# Flatsat_v1.net
KiCad netlist of a schematic drawn in EAGLE
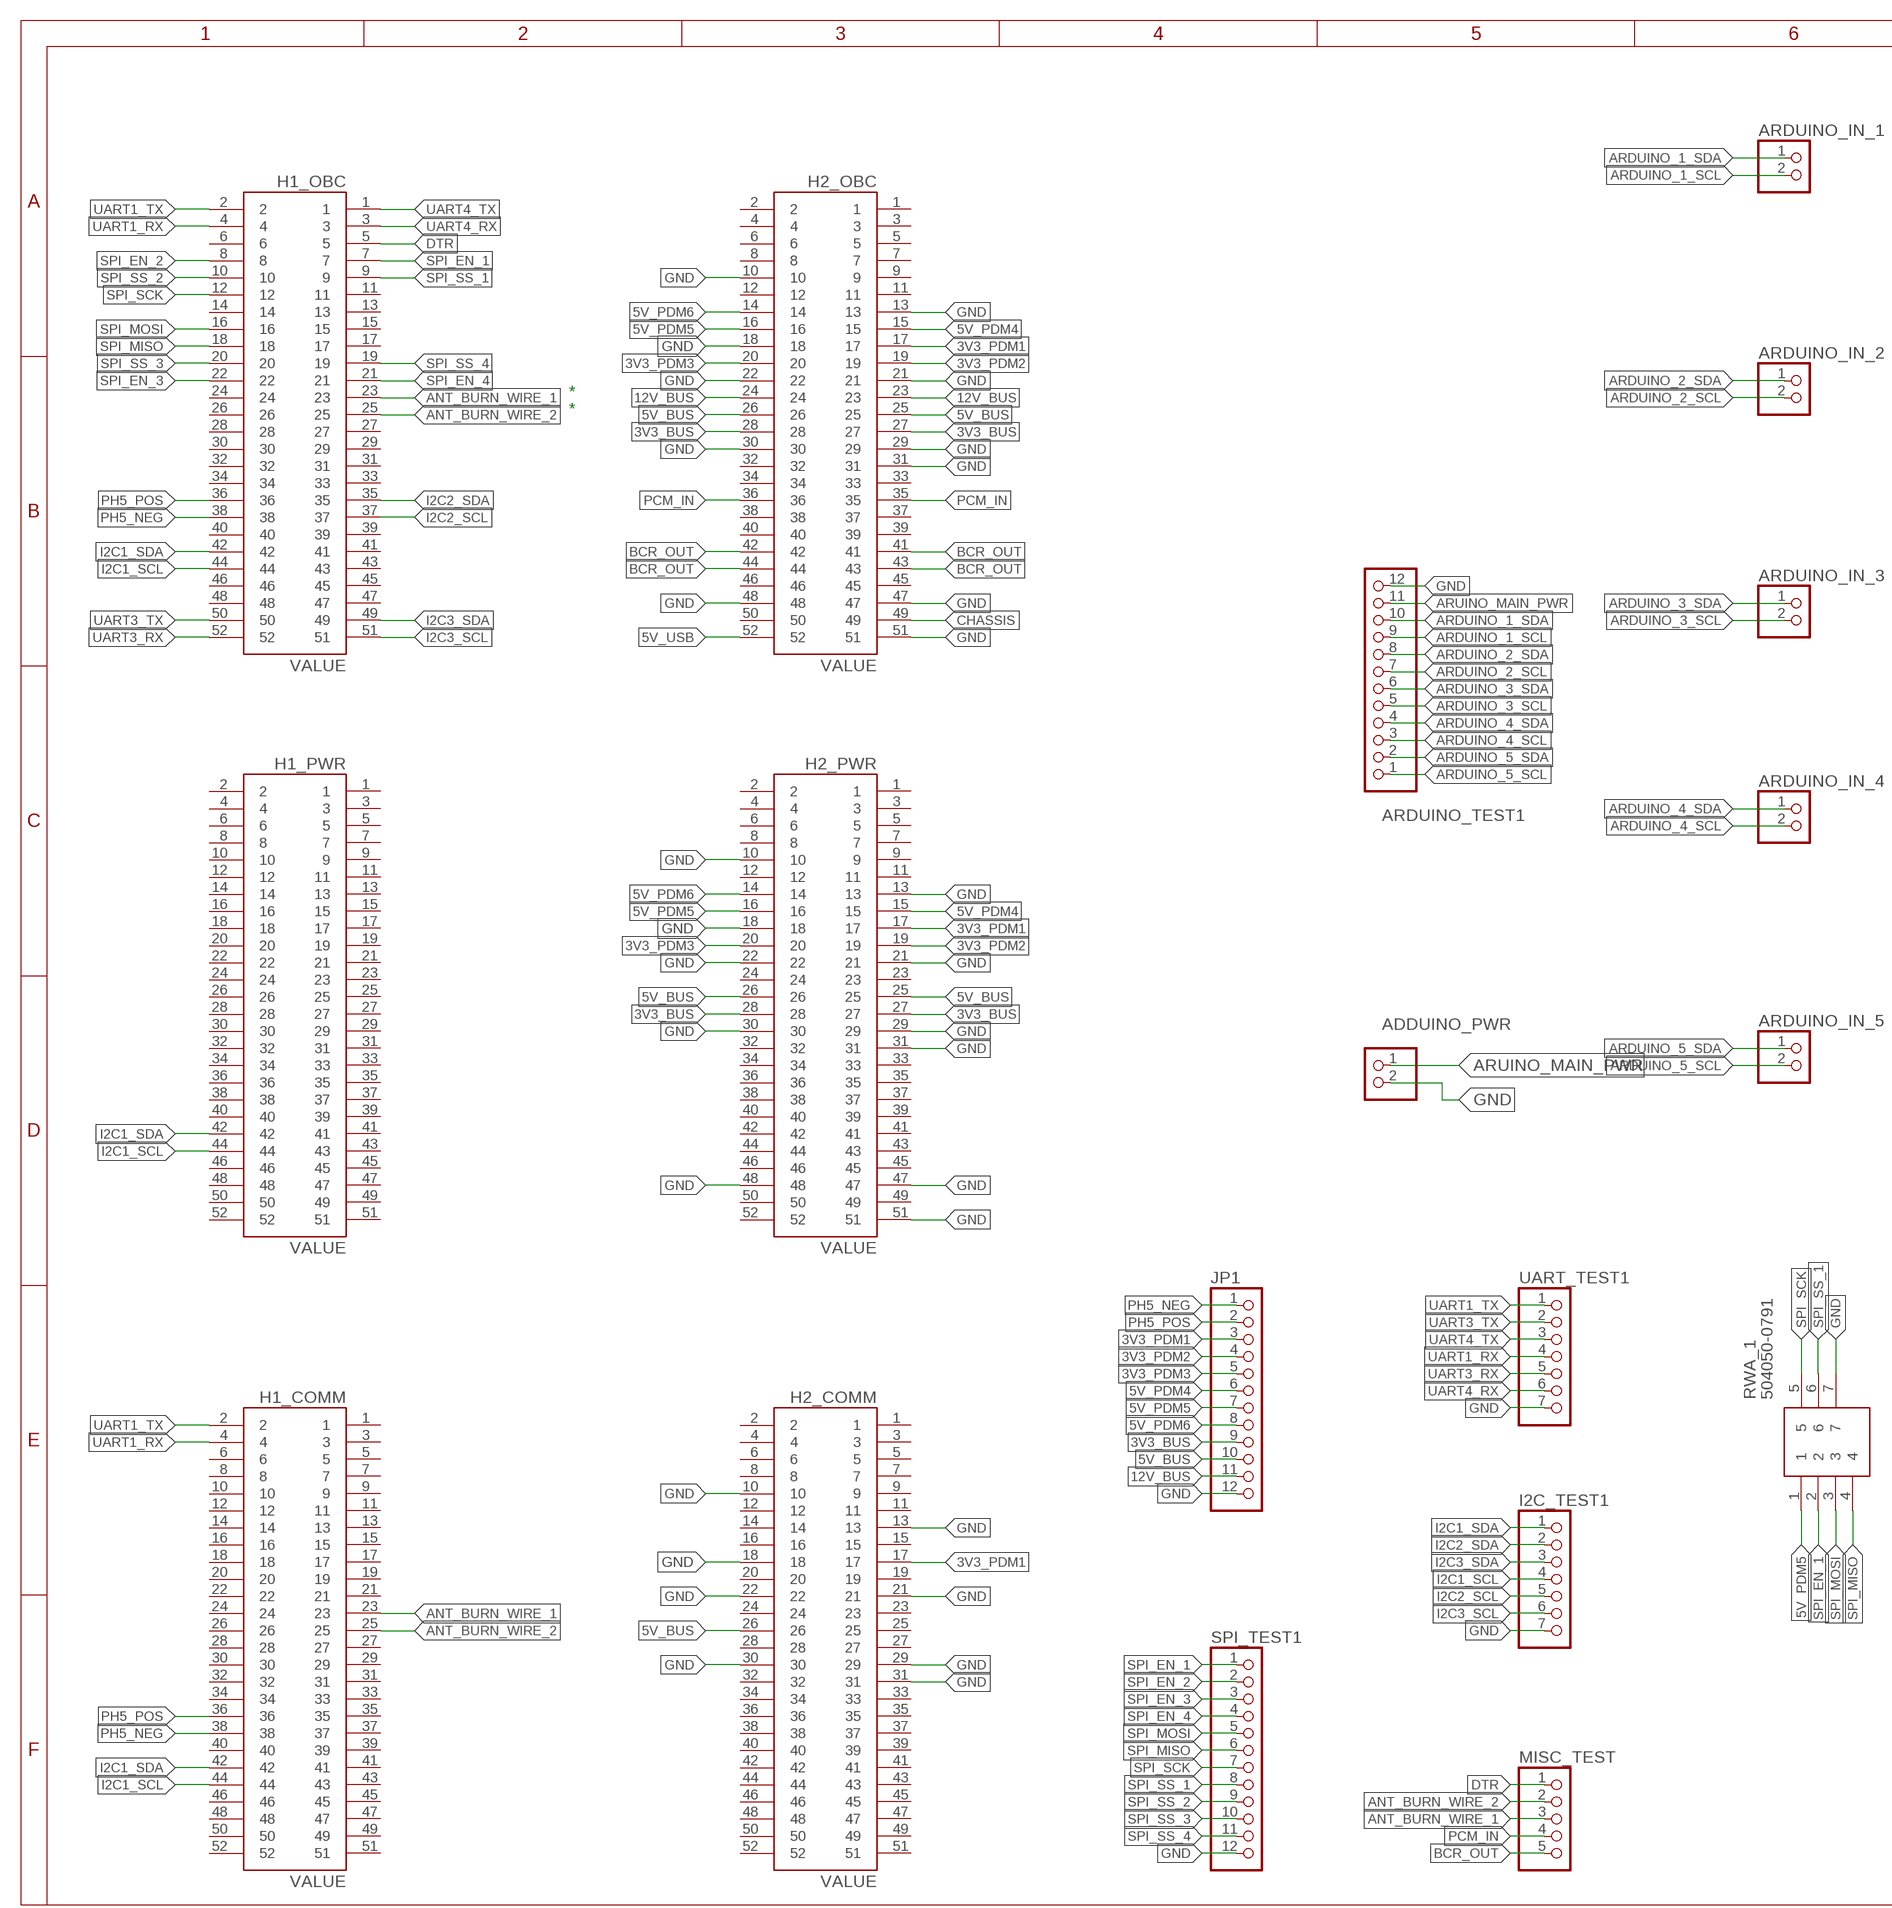
[diagram p0: schematic, sheet 1, part 1 of 2]
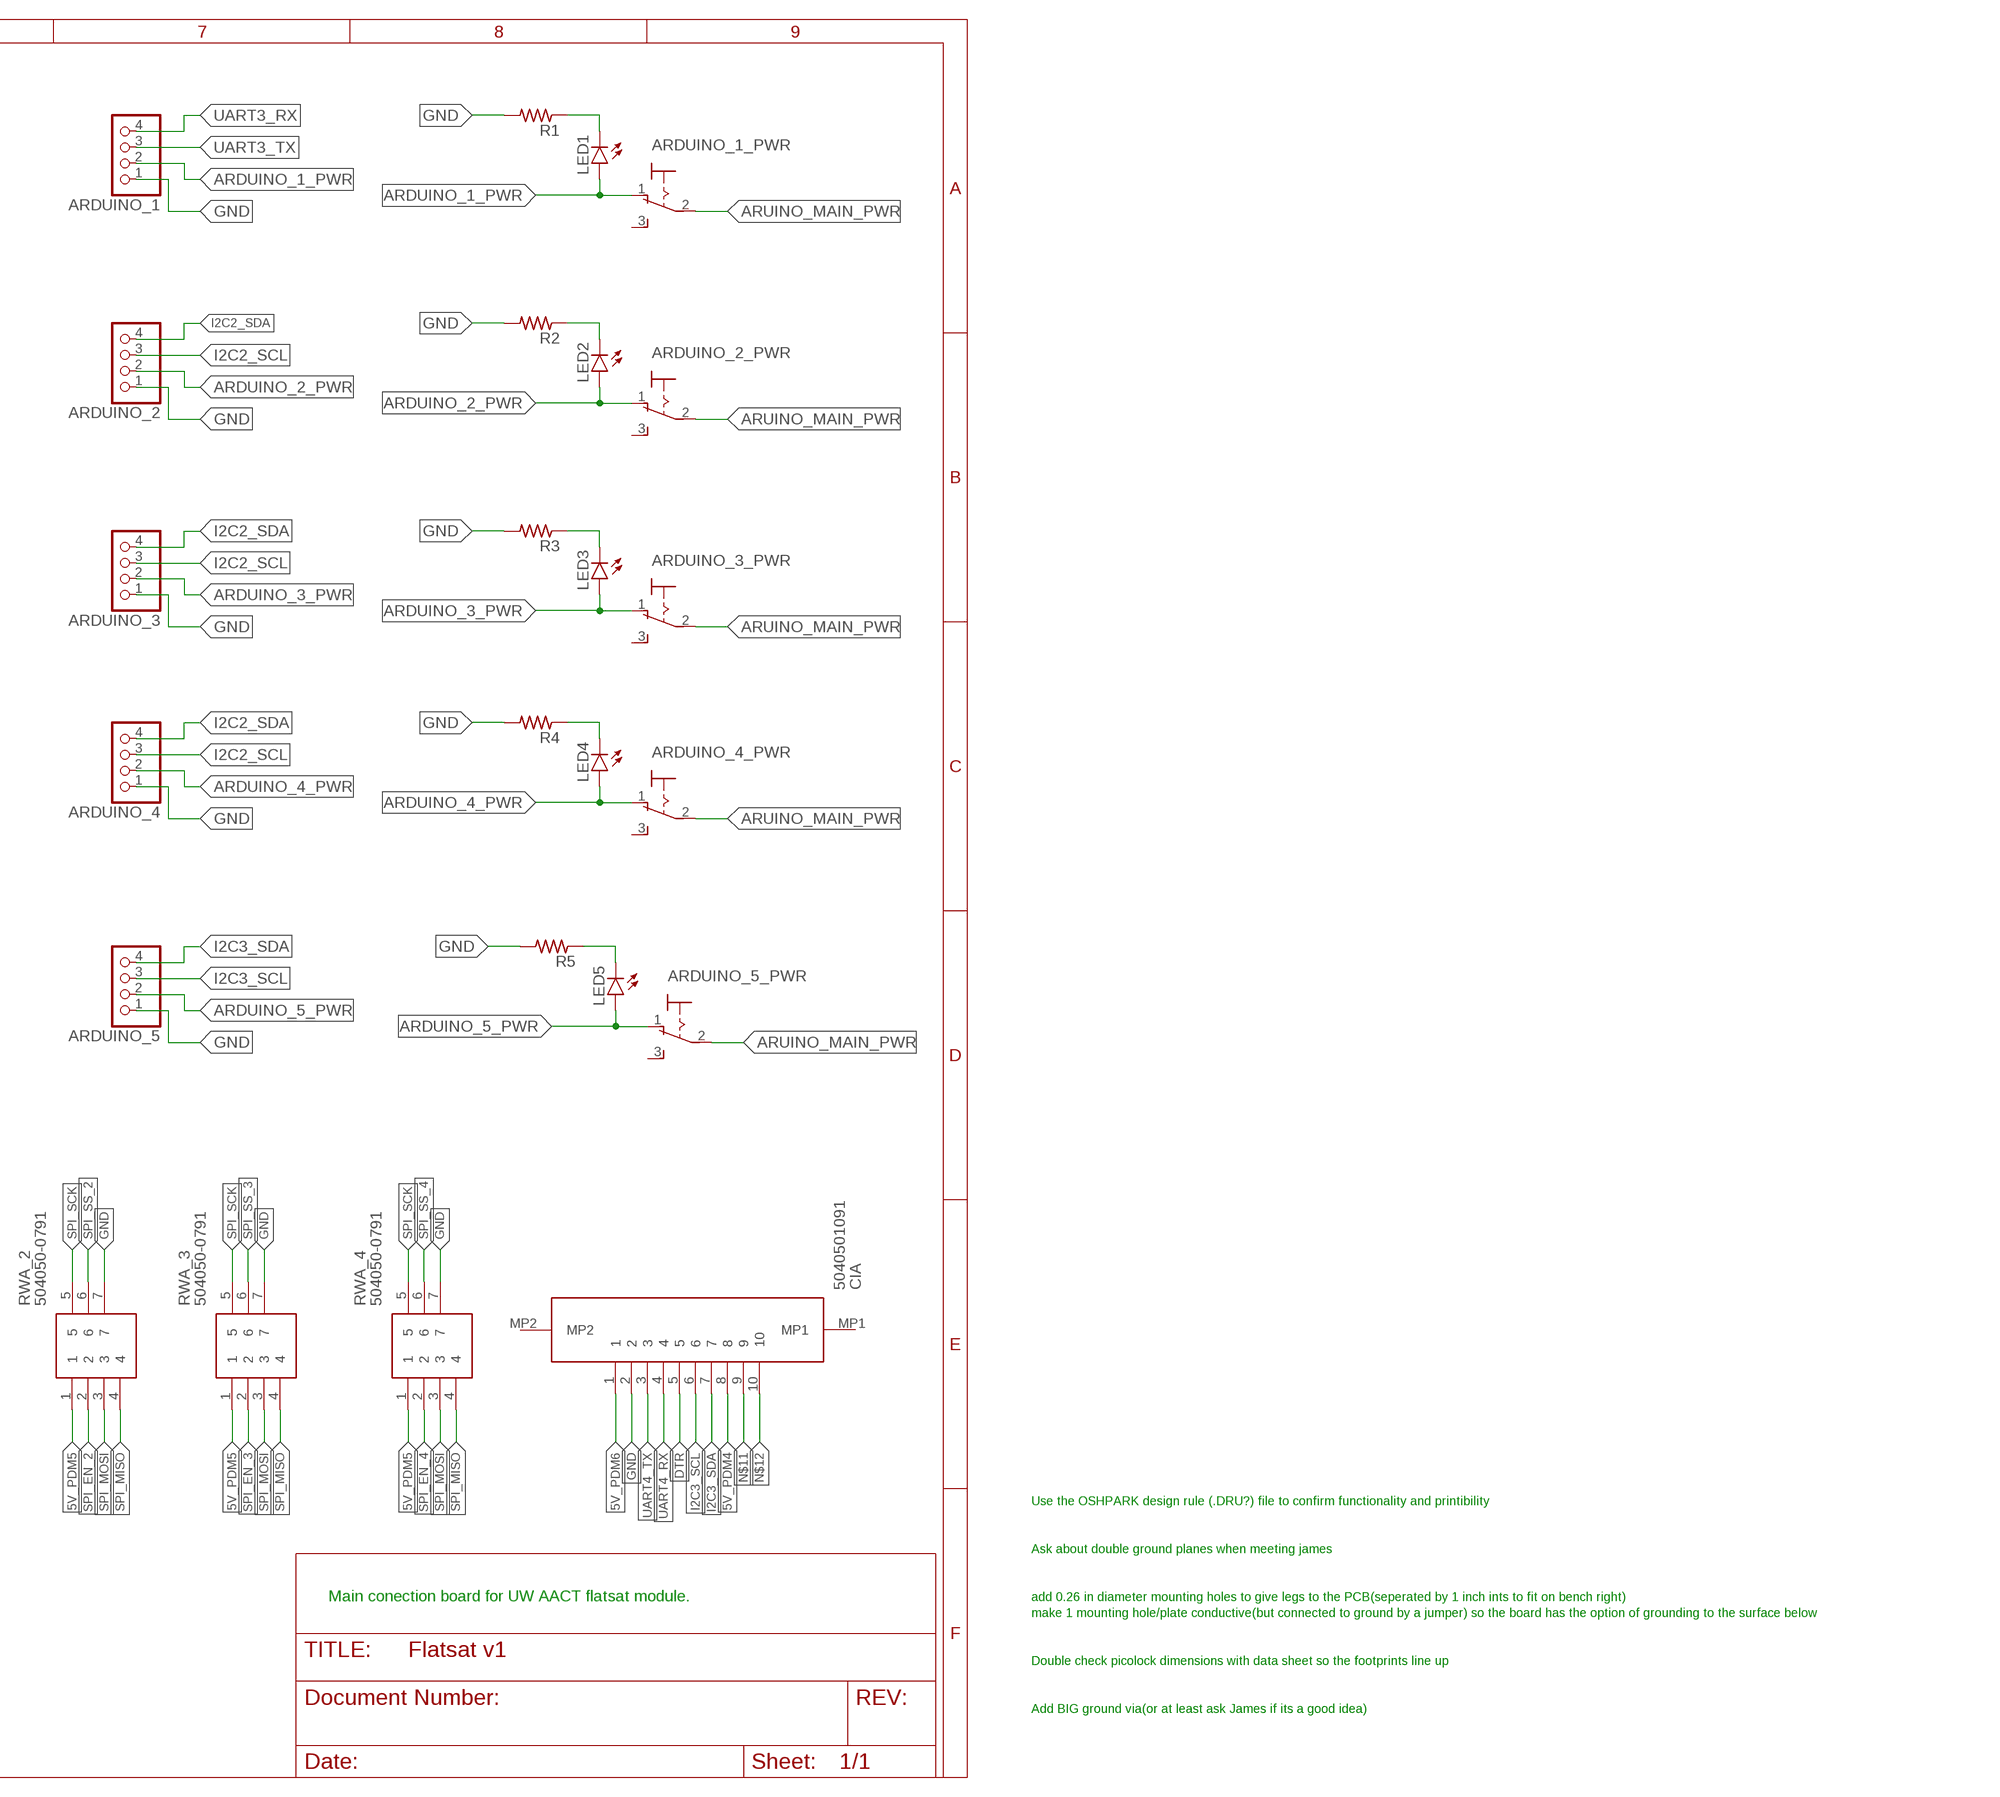
[diagram p1: schematic, sheet 1, part 2 of 2]

(export (version "E")
  (design (tool "Eeschema 10.0.6"))
  (components
    (comp (ref "ADDUINO_PWR")
      (value "PINHD-1X2")
      (footprint "eagle-import:1X02")
      (libsource (lib "eagle-import") (part "PINHD-1X2"))
    )
    (comp (ref "ARDUINO_1")
      (value "PINHD-1X4")
      (footprint "eagle-import:1X04")
      (libsource (lib "eagle-import") (part "PINHD-1X4"))
    )
    (comp (ref "ARDUINO_1_PWR")
      (value "M9040P")
      (footprint "eagle-import:M9040P")
      (libsource (lib "eagle-import") (part "M9040P"))
    )
    (comp (ref "ARDUINO_2")
      (value "PINHD-1X4")
      (footprint "eagle-import:1X04")
      (libsource (lib "eagle-import") (part "PINHD-1X4"))
    )
    (comp (ref "ARDUINO_2_PWR")
      (value "M9040P")
      (footprint "eagle-import:M9040P")
      (libsource (lib "eagle-import") (part "M9040P"))
    )
    (comp (ref "ARDUINO_3")
      (value "PINHD-1X4")
      (footprint "eagle-import:1X04")
      (libsource (lib "eagle-import") (part "PINHD-1X4"))
    )
    (comp (ref "ARDUINO_3_PWR")
      (value "M9040P")
      (footprint "eagle-import:M9040P")
      (libsource (lib "eagle-import") (part "M9040P"))
    )
    (comp (ref "ARDUINO_4")
      (value "PINHD-1X4")
      (footprint "eagle-import:1X04")
      (libsource (lib "eagle-import") (part "PINHD-1X4"))
    )
    (comp (ref "ARDUINO_4_PWR")
      (value "M9040P")
      (footprint "eagle-import:M9040P")
      (libsource (lib "eagle-import") (part "M9040P"))
    )
    (comp (ref "ARDUINO_5")
      (value "PINHD-1X4")
      (footprint "eagle-import:1X04")
      (libsource (lib "eagle-import") (part "PINHD-1X4"))
    )
    (comp (ref "ARDUINO_5_PWR")
      (value "M9040P")
      (footprint "eagle-import:M9040P")
      (libsource (lib "eagle-import") (part "M9040P"))
    )
    (comp (ref "ARDUINO_IN_1")
      (value "PINHD-1X2")
      (footprint "eagle-import:1X02")
      (libsource (lib "eagle-import") (part "PINHD-1X2"))
    )
    (comp (ref "ARDUINO_IN_2")
      (value "PINHD-1X2")
      (footprint "eagle-import:1X02")
      (libsource (lib "eagle-import") (part "PINHD-1X2"))
    )
    (comp (ref "ARDUINO_IN_3")
      (value "PINHD-1X2")
      (footprint "eagle-import:1X02")
      (libsource (lib "eagle-import") (part "PINHD-1X2"))
    )
    (comp (ref "ARDUINO_IN_4")
      (value "PINHD-1X2")
      (footprint "eagle-import:1X02")
      (libsource (lib "eagle-import") (part "PINHD-1X2"))
    )
    (comp (ref "ARDUINO_IN_5")
      (value "PINHD-1X2")
      (footprint "eagle-import:1X02")
      (libsource (lib "eagle-import") (part "PINHD-1X2"))
    )
    (comp (ref "ARDUINO_TEST1")
      (value "PINHD-1X12")
      (footprint "eagle-import:1X12")
      (libsource (lib "eagle-import") (part "PINHD-1X12"))
    )
    (comp (ref "CIA")
      (value "5040501091")
      (footprint "eagle-import:5040501091")
      (libsource (lib "eagle-import") (part "5040501091"))
    )
    (comp (ref "H1_COMM")
      (value "ESQ-126-39-G-D_ESQ-126-39-G-D")
      (footprint "eagle-import:ESQ-126-39-G-D_SAMTEC_ESQ-126-39-G-D")
      (fields
        (field (name "DIGI-KEY_PART_NUMBER") "SAM10462-ND")
        (field (name "MF") "Samtec")
        (field (name "MP") "ESQ-126-39-G-D")
      )
      (libsource (lib "eagle-import") (part "ESQ-126-39-G-D_ESQ-126-39-G-D"))
    )
    (comp (ref "H1_OBC")
      (value "ESQ-126-39-G-D_ESQ-126-39-G-D")
      (footprint "eagle-import:ESQ-126-39-G-D_SAMTEC_ESQ-126-39-G-D")
      (fields
        (field (name "DIGI-KEY_PART_NUMBER") "SAM10462-ND")
        (field (name "MF") "Samtec")
        (field (name "MP") "ESQ-126-39-G-D")
      )
      (libsource (lib "eagle-import") (part "ESQ-126-39-G-D_ESQ-126-39-G-D"))
    )
    (comp (ref "H1_PWR")
      (value "ESQ-126-39-G-D_ESQ-126-39-G-D")
      (footprint "eagle-import:ESQ-126-39-G-D_SAMTEC_ESQ-126-39-G-D")
      (fields
        (field (name "DIGI-KEY_PART_NUMBER") "SAM10462-ND")
        (field (name "MF") "Samtec")
        (field (name "MP") "ESQ-126-39-G-D")
      )
      (libsource (lib "eagle-import") (part "ESQ-126-39-G-D_ESQ-126-39-G-D"))
    )
    (comp (ref "H2_COMM")
      (value "ESQ-126-39-G-D_ESQ-126-39-G-D")
      (footprint "eagle-import:ESQ-126-39-G-D_SAMTEC_ESQ-126-39-G-D")
      (fields
        (field (name "DIGI-KEY_PART_NUMBER") "SAM10462-ND")
        (field (name "MF") "Samtec")
        (field (name "MP") "ESQ-126-39-G-D")
      )
      (libsource (lib "eagle-import") (part "ESQ-126-39-G-D_ESQ-126-39-G-D"))
    )
    (comp (ref "H2_OBC")
      (value "ESQ-126-39-G-D_ESQ-126-39-G-D")
      (footprint "eagle-import:ESQ-126-39-G-D_SAMTEC_ESQ-126-39-G-D")
      (fields
        (field (name "DIGI-KEY_PART_NUMBER") "SAM10462-ND")
        (field (name "MF") "Samtec")
        (field (name "MP") "ESQ-126-39-G-D")
      )
      (libsource (lib "eagle-import") (part "ESQ-126-39-G-D_ESQ-126-39-G-D"))
    )
    (comp (ref "H2_PWR")
      (value "ESQ-126-39-G-D_ESQ-126-39-G-D")
      (footprint "eagle-import:ESQ-126-39-G-D_SAMTEC_ESQ-126-39-G-D")
      (fields
        (field (name "DIGI-KEY_PART_NUMBER") "SAM10462-ND")
        (field (name "MF") "Samtec")
        (field (name "MP") "ESQ-126-39-G-D")
      )
      (libsource (lib "eagle-import") (part "ESQ-126-39-G-D_ESQ-126-39-G-D"))
    )
    (comp (ref "I2C_TEST1")
      (value "PINHD-1X7")
      (footprint "eagle-import:1X07")
      (libsource (lib "eagle-import") (part "PINHD-1X7"))
    )
    (comp (ref "JP1")
      (value "PINHD-1X12")
      (footprint "eagle-import:1X12")
      (libsource (lib "eagle-import") (part "PINHD-1X12"))
    )
    (comp (ref "LED1")
      (value "TLLR4400")
      (footprint "eagle-import:LED3MM")
      (fields (field (name "MF") "VISHAY SEMICONDUCTOR"))
      (libsource (lib "eagle-import") (part "TLLR4400"))
    )
    (comp (ref "LED2")
      (value "TLLR4400")
      (footprint "eagle-import:LED3MM")
      (fields (field (name "MF") "VISHAY SEMICONDUCTOR"))
      (libsource (lib "eagle-import") (part "TLLR4400"))
    )
    (comp (ref "LED3")
      (value "TLLR4400")
      (footprint "eagle-import:LED3MM")
      (fields (field (name "MF") "VISHAY SEMICONDUCTOR"))
      (libsource (lib "eagle-import") (part "TLLR4400"))
    )
    (comp (ref "LED4")
      (value "TLLR4400")
      (footprint "eagle-import:LED3MM")
      (fields (field (name "MF") "VISHAY SEMICONDUCTOR"))
      (libsource (lib "eagle-import") (part "TLLR4400"))
    )
    (comp (ref "LED5")
      (value "TLLR4400")
      (footprint "eagle-import:LED3MM")
      (fields (field (name "MF") "VISHAY SEMICONDUCTOR"))
      (libsource (lib "eagle-import") (part "TLLR4400"))
    )
    (comp (ref "MISC_TEST")
      (value "PINHD-1X5")
      (footprint "eagle-import:1X05")
      (libsource (lib "eagle-import") (part "PINHD-1X5"))
    )
    (comp (ref "R1")
      (value "R-US_R0805W")
      (footprint "eagle-import:R0805W")
      (libsource (lib "eagle-import") (part "R-US_R0805W"))
    )
    (comp (ref "R2")
      (value "R-US_R0805W")
      (footprint "eagle-import:R0805W")
      (libsource (lib "eagle-import") (part "R-US_R0805W"))
    )
    (comp (ref "R3")
      (value "R-US_R0805W")
      (footprint "eagle-import:R0805W")
      (libsource (lib "eagle-import") (part "R-US_R0805W"))
    )
    (comp (ref "R4")
      (value "R-US_R0805W")
      (footprint "eagle-import:R0805W")
      (libsource (lib "eagle-import") (part "R-US_R0805W"))
    )
    (comp (ref "R5")
      (value "R-US_R0805W")
      (footprint "eagle-import:R0805W")
      (libsource (lib "eagle-import") (part "R-US_R0805W"))
    )
    (comp (ref "RWA_1")
      (value "504050-0791")
      (footprint "eagle-import:504050-0791")
      (fields (field (name "MOUSER_PART_NUMBER") "538-504050-0791"))
      (libsource (lib "eagle-import") (part "504050-0791"))
    )
    (comp (ref "RWA_2")
      (value "504050-0791")
      (footprint "eagle-import:504050-0791")
      (fields (field (name "MOUSER_PART_NUMBER") "538-504050-0791"))
      (libsource (lib "eagle-import") (part "504050-0791"))
    )
    (comp (ref "RWA_3")
      (value "504050-0791")
      (footprint "eagle-import:504050-0791")
      (fields (field (name "MOUSER_PART_NUMBER") "538-504050-0791"))
      (libsource (lib "eagle-import") (part "504050-0791"))
    )
    (comp (ref "RWA_4")
      (value "504050-0791")
      (footprint "eagle-import:504050-0791")
      (fields (field (name "MOUSER_PART_NUMBER") "538-504050-0791"))
      (libsource (lib "eagle-import") (part "504050-0791"))
    )
    (comp (ref "SPI_TEST1")
      (value "PINHD-1X12")
      (footprint "eagle-import:1X12")
      (libsource (lib "eagle-import") (part "PINHD-1X12"))
    )
    (comp (ref "UART_TEST1")
      (value "PINHD-1X7")
      (footprint "eagle-import:1X07")
      (libsource (lib "eagle-import") (part "PINHD-1X7"))
    )
  )
  (nets
    (net (code "1") (name "3V3_BUS") (class "Default")
      (node (ref "H2_OBC") (pin "27") (pinfunction "27_27") (pintype "passive"))
      (node (ref "H2_OBC") (pin "28") (pinfunction "28_28") (pintype "passive"))
      (node (ref "H2_PWR") (pin "27") (pinfunction "27_27") (pintype "passive"))
      (node (ref "H2_PWR") (pin "28") (pinfunction "28_28") (pintype "passive"))
      (node (ref "JP1") (pin "9") (pinfunction "9_9") (pintype "passive"))
    )
    (net (code "2") (name "3V3_PDM1") (class "Default")
      (node (ref "H2_COMM") (pin "17") (pinfunction "17_17") (pintype "passive"))
      (node (ref "H2_OBC") (pin "17") (pinfunction "17_17") (pintype "passive"))
      (node (ref "H2_PWR") (pin "17") (pinfunction "17_17") (pintype "passive"))
      (node (ref "JP1") (pin "3") (pinfunction "3_3") (pintype "passive"))
    )
    (net (code "3") (name "3V3_PDM2") (class "Default")
      (node (ref "H2_OBC") (pin "19") (pinfunction "19_19") (pintype "passive"))
      (node (ref "H2_PWR") (pin "19") (pinfunction "19_19") (pintype "passive"))
      (node (ref "JP1") (pin "4") (pinfunction "4_4") (pintype "passive"))
    )
    (net (code "4") (name "3V3_PDM3") (class "Default")
      (node (ref "H2_OBC") (pin "20") (pinfunction "20_20") (pintype "passive"))
      (node (ref "H2_PWR") (pin "20") (pinfunction "20_20") (pintype "passive"))
      (node (ref "JP1") (pin "5") (pinfunction "5_5") (pintype "passive"))
    )
    (net (code "5") (name "5V_BUS") (class "Default")
      (node (ref "H2_COMM") (pin "26") (pinfunction "26_26") (pintype "passive"))
      (node (ref "H2_OBC") (pin "25") (pinfunction "25_25") (pintype "passive"))
      (node (ref "H2_OBC") (pin "26") (pinfunction "26_26") (pintype "passive"))
      (node (ref "H2_PWR") (pin "25") (pinfunction "25_25") (pintype "passive"))
      (node (ref "H2_PWR") (pin "26") (pinfunction "26_26") (pintype "passive"))
      (node (ref "JP1") (pin "10") (pinfunction "10_10") (pintype "passive"))
    )
    (net (code "6") (name "5V_PDM4") (class "Default")
      (node (ref "CIA") (pin "8") (pinfunction "8_8") (pintype "bidirectional"))
      (node (ref "H2_OBC") (pin "15") (pinfunction "15_15") (pintype "passive"))
      (node (ref "H2_PWR") (pin "15") (pinfunction "15_15") (pintype "passive"))
      (node (ref "JP1") (pin "6") (pinfunction "6_6") (pintype "passive"))
    )
    (net (code "7") (name "5V_PDM5") (class "Default")
      (node (ref "H2_OBC") (pin "16") (pinfunction "16_16") (pintype "passive"))
      (node (ref "H2_PWR") (pin "16") (pinfunction "16_16") (pintype "passive"))
      (node (ref "JP1") (pin "7") (pinfunction "7_7") (pintype "passive"))
      (node (ref "RWA_1") (pin "1") (pinfunction "1_1") (pintype "bidirectional"))
      (node (ref "RWA_2") (pin "1") (pinfunction "1_1") (pintype "bidirectional"))
      (node (ref "RWA_3") (pin "1") (pinfunction "1_1") (pintype "bidirectional"))
      (node (ref "RWA_4") (pin "1") (pinfunction "1_1") (pintype "bidirectional"))
    )
    (net (code "8") (name "5V_PDM6") (class "Default")
      (node (ref "CIA") (pin "1") (pinfunction "1_1") (pintype "bidirectional"))
      (node (ref "H2_OBC") (pin "14") (pinfunction "14_14") (pintype "passive"))
      (node (ref "H2_PWR") (pin "14") (pinfunction "14_14") (pintype "passive"))
      (node (ref "JP1") (pin "8") (pinfunction "8_8") (pintype "passive"))
    )
    (net (code "9") (name "5V_USB") (class "Default")
      (node (ref "H2_OBC") (pin "52") (pinfunction "52_52") (pintype "passive"))
    )
    (net (code "10") (name "12V_BUS") (class "Default")
      (node (ref "H2_OBC") (pin "23") (pinfunction "23_23") (pintype "passive"))
      (node (ref "H2_OBC") (pin "24") (pinfunction "24_24") (pintype "passive"))
      (node (ref "JP1") (pin "11") (pinfunction "11_11") (pintype "passive"))
    )
    (net (code "11") (name "ANT_BURN_WIRE_1") (class "Default")
      (node (ref "H1_COMM") (pin "23") (pinfunction "23_23") (pintype "passive"))
      (node (ref "H1_OBC") (pin "23") (pinfunction "23_23") (pintype "passive"))
      (node (ref "MISC_TEST") (pin "3") (pinfunction "3_3") (pintype "passive"))
    )
    (net (code "12") (name "ANT_BURN_WIRE_2") (class "Default")
      (node (ref "H1_COMM") (pin "25") (pinfunction "25_25") (pintype "passive"))
      (node (ref "H1_OBC") (pin "25") (pinfunction "25_25") (pintype "passive"))
      (node (ref "MISC_TEST") (pin "2") (pinfunction "2_2") (pintype "passive"))
    )
    (net (code "13") (name "ARDUINO_1_PWR") (class "Default")
      (node (ref "ARDUINO_1") (pin "2") (pinfunction "2_2") (pintype "passive"))
      (node (ref "ARDUINO_1_PWR") (pin "1") (pinfunction "O_1") (pintype "passive"))
      (node (ref "LED1") (pin "A") (pinfunction "A_A") (pintype "passive"))
    )
    (net (code "14") (name "ARDUINO_1_SCL") (class "Default")
      (node (ref "ARDUINO_IN_1") (pin "2") (pinfunction "2_2") (pintype "passive"))
      (node (ref "ARDUINO_TEST1") (pin "9") (pinfunction "9_9") (pintype "passive"))
    )
    (net (code "15") (name "ARDUINO_1_SDA") (class "Default")
      (node (ref "ARDUINO_IN_1") (pin "1") (pinfunction "1_1") (pintype "passive"))
      (node (ref "ARDUINO_TEST1") (pin "10") (pinfunction "10_10") (pintype "passive"))
    )
    (net (code "16") (name "ARDUINO_2_PWR") (class "Default")
      (node (ref "ARDUINO_2") (pin "2") (pinfunction "2_2") (pintype "passive"))
      (node (ref "ARDUINO_2_PWR") (pin "1") (pinfunction "O_1") (pintype "passive"))
      (node (ref "LED2") (pin "A") (pinfunction "A_A") (pintype "passive"))
    )
    (net (code "17") (name "ARDUINO_2_SCL") (class "Default")
      (node (ref "ARDUINO_IN_2") (pin "2") (pinfunction "2_2") (pintype "passive"))
      (node (ref "ARDUINO_TEST1") (pin "7") (pinfunction "7_7") (pintype "passive"))
    )
    (net (code "18") (name "ARDUINO_2_SDA") (class "Default")
      (node (ref "ARDUINO_IN_2") (pin "1") (pinfunction "1_1") (pintype "passive"))
      (node (ref "ARDUINO_TEST1") (pin "8") (pinfunction "8_8") (pintype "passive"))
    )
    (net (code "19") (name "ARDUINO_3_PWR") (class "Default")
      (node (ref "ARDUINO_3") (pin "2") (pinfunction "2_2") (pintype "passive"))
      (node (ref "ARDUINO_3_PWR") (pin "1") (pinfunction "O_1") (pintype "passive"))
      (node (ref "LED3") (pin "A") (pinfunction "A_A") (pintype "passive"))
    )
    (net (code "20") (name "ARDUINO_3_SCL") (class "Default")
      (node (ref "ARDUINO_IN_3") (pin "2") (pinfunction "2_2") (pintype "passive"))
      (node (ref "ARDUINO_TEST1") (pin "5") (pinfunction "5_5") (pintype "passive"))
    )
    (net (code "21") (name "ARDUINO_3_SDA") (class "Default")
      (node (ref "ARDUINO_IN_3") (pin "1") (pinfunction "1_1") (pintype "passive"))
      (node (ref "ARDUINO_TEST1") (pin "6") (pinfunction "6_6") (pintype "passive"))
    )
    (net (code "22") (name "ARDUINO_4_PWR") (class "Default")
      (node (ref "ARDUINO_4") (pin "2") (pinfunction "2_2") (pintype "passive"))
      (node (ref "ARDUINO_4_PWR") (pin "1") (pinfunction "O_1") (pintype "passive"))
      (node (ref "LED4") (pin "A") (pinfunction "A_A") (pintype "passive"))
    )
    (net (code "23") (name "ARDUINO_4_SCL") (class "Default")
      (node (ref "ARDUINO_IN_4") (pin "2") (pinfunction "2_2") (pintype "passive"))
      (node (ref "ARDUINO_TEST1") (pin "3") (pinfunction "3_3") (pintype "passive"))
    )
    (net (code "24") (name "ARDUINO_4_SDA") (class "Default")
      (node (ref "ARDUINO_IN_4") (pin "1") (pinfunction "1_1") (pintype "passive"))
      (node (ref "ARDUINO_TEST1") (pin "4") (pinfunction "4_4") (pintype "passive"))
    )
    (net (code "25") (name "ARDUINO_5_PWR") (class "Default")
      (node (ref "ARDUINO_5") (pin "2") (pinfunction "2_2") (pintype "passive"))
      (node (ref "ARDUINO_5_PWR") (pin "1") (pinfunction "O_1") (pintype "passive"))
      (node (ref "LED5") (pin "A") (pinfunction "A_A") (pintype "passive"))
    )
    (net (code "26") (name "ARDUINO_5_SCL") (class "Default")
      (node (ref "ARDUINO_IN_5") (pin "2") (pinfunction "2_2") (pintype "passive"))
      (node (ref "ARDUINO_TEST1") (pin "1") (pinfunction "1_1") (pintype "passive"))
    )
    (net (code "27") (name "ARDUINO_5_SDA") (class "Default")
      (node (ref "ARDUINO_IN_5") (pin "1") (pinfunction "1_1") (pintype "passive"))
      (node (ref "ARDUINO_TEST1") (pin "2") (pinfunction "2_2") (pintype "passive"))
    )
    (net (code "28") (name "ARUINO_MAIN_PWR") (class "Default")
      (node (ref "ADDUINO_PWR") (pin "1") (pinfunction "1_1") (pintype "passive"))
      (node (ref "ARDUINO_1_PWR") (pin "2") (pinfunction "P_2") (pintype "passive"))
      (node (ref "ARDUINO_2_PWR") (pin "2") (pinfunction "P_2") (pintype "passive"))
      (node (ref "ARDUINO_3_PWR") (pin "2") (pinfunction "P_2") (pintype "passive"))
      (node (ref "ARDUINO_4_PWR") (pin "2") (pinfunction "P_2") (pintype "passive"))
      (node (ref "ARDUINO_5_PWR") (pin "2") (pinfunction "P_2") (pintype "passive"))
      (node (ref "ARDUINO_TEST1") (pin "11") (pinfunction "11_11") (pintype "passive"))
    )
    (net (code "29") (name "BCR_OUT") (class "Default")
      (node (ref "H2_OBC") (pin "41") (pinfunction "41_41") (pintype "passive"))
      (node (ref "H2_OBC") (pin "42") (pinfunction "42_42") (pintype "passive"))
      (node (ref "H2_OBC") (pin "43") (pinfunction "43_43") (pintype "passive"))
      (node (ref "H2_OBC") (pin "44") (pinfunction "44_44") (pintype "passive"))
      (node (ref "MISC_TEST") (pin "5") (pinfunction "5_5") (pintype "passive"))
    )
    (net (code "30") (name "CHASSIS") (class "Default")
      (node (ref "H2_OBC") (pin "49") (pinfunction "49_49") (pintype "passive"))
    )
    (net (code "31") (name "DTR") (class "Default")
      (node (ref "CIA") (pin "5") (pinfunction "5_5") (pintype "bidirectional"))
      (node (ref "H1_OBC") (pin "5") (pinfunction "5_5") (pintype "passive"))
      (node (ref "MISC_TEST") (pin "1") (pinfunction "1_1") (pintype "passive"))
    )
    (net (code "32") (name "GND") (class "Default")
      (node (ref "ADDUINO_PWR") (pin "2") (pinfunction "2_2") (pintype "passive"))
      (node (ref "ARDUINO_1") (pin "1") (pinfunction "1_1") (pintype "passive"))
      (node (ref "ARDUINO_2") (pin "1") (pinfunction "1_1") (pintype "passive"))
      (node (ref "ARDUINO_3") (pin "1") (pinfunction "1_1") (pintype "passive"))
      (node (ref "ARDUINO_4") (pin "1") (pinfunction "1_1") (pintype "passive"))
      (node (ref "ARDUINO_5") (pin "1") (pinfunction "1_1") (pintype "passive"))
      (node (ref "ARDUINO_TEST1") (pin "12") (pinfunction "12_12") (pintype "passive"))
      (node (ref "CIA") (pin "2") (pinfunction "2_2") (pintype "bidirectional"))
      (node (ref "H2_COMM") (pin "10") (pinfunction "10_10") (pintype "passive"))
      (node (ref "H2_COMM") (pin "13") (pinfunction "13_13") (pintype "passive"))
      (node (ref "H2_COMM") (pin "18") (pinfunction "18_18") (pintype "passive"))
      (node (ref "H2_COMM") (pin "21") (pinfunction "21_21") (pintype "passive"))
      (node (ref "H2_COMM") (pin "22") (pinfunction "22_22") (pintype "passive"))
      (node (ref "H2_COMM") (pin "29") (pinfunction "29_29") (pintype "passive"))
      (node (ref "H2_COMM") (pin "30") (pinfunction "30_30") (pintype "passive"))
      (node (ref "H2_COMM") (pin "31") (pinfunction "31_31") (pintype "passive"))
      (node (ref "H2_OBC") (pin "10") (pinfunction "10_10") (pintype "passive"))
      (node (ref "H2_OBC") (pin "13") (pinfunction "13_13") (pintype "passive"))
      (node (ref "H2_OBC") (pin "18") (pinfunction "18_18") (pintype "passive"))
      (node (ref "H2_OBC") (pin "21") (pinfunction "21_21") (pintype "passive"))
      (node (ref "H2_OBC") (pin "22") (pinfunction "22_22") (pintype "passive"))
      (node (ref "H2_OBC") (pin "29") (pinfunction "29_29") (pintype "passive"))
      (node (ref "H2_OBC") (pin "30") (pinfunction "30_30") (pintype "passive"))
      (node (ref "H2_OBC") (pin "31") (pinfunction "31_31") (pintype "passive"))
      (node (ref "H2_OBC") (pin "47") (pinfunction "47_47") (pintype "passive"))
      (node (ref "H2_OBC") (pin "48") (pinfunction "48_48") (pintype "passive"))
      (node (ref "H2_OBC") (pin "51") (pinfunction "51_51") (pintype "passive"))
      (node (ref "H2_PWR") (pin "10") (pinfunction "10_10") (pintype "passive"))
      (node (ref "H2_PWR") (pin "13") (pinfunction "13_13") (pintype "passive"))
      (node (ref "H2_PWR") (pin "18") (pinfunction "18_18") (pintype "passive"))
      (node (ref "H2_PWR") (pin "21") (pinfunction "21_21") (pintype "passive"))
      (node (ref "H2_PWR") (pin "22") (pinfunction "22_22") (pintype "passive"))
      (node (ref "H2_PWR") (pin "29") (pinfunction "29_29") (pintype "passive"))
      (node (ref "H2_PWR") (pin "30") (pinfunction "30_30") (pintype "passive"))
      (node (ref "H2_PWR") (pin "31") (pinfunction "31_31") (pintype "passive"))
      (node (ref "H2_PWR") (pin "47") (pinfunction "47_47") (pintype "passive"))
      (node (ref "H2_PWR") (pin "48") (pinfunction "48_48") (pintype "passive"))
      (node (ref "H2_PWR") (pin "51") (pinfunction "51_51") (pintype "passive"))
      (node (ref "I2C_TEST1") (pin "7") (pinfunction "7_7") (pintype "passive"))
      (node (ref "JP1") (pin "12") (pinfunction "12_12") (pintype "passive"))
      (node (ref "R1") (pin "2") (pinfunction "2_2") (pintype "passive"))
      (node (ref "R2") (pin "2") (pinfunction "2_2") (pintype "passive"))
      (node (ref "R3") (pin "2") (pinfunction "2_2") (pintype "passive"))
      (node (ref "R4") (pin "2") (pinfunction "2_2") (pintype "passive"))
      (node (ref "R5") (pin "2") (pinfunction "2_2") (pintype "passive"))
      (node (ref "RWA_1") (pin "7") (pinfunction "7_7") (pintype "bidirectional"))
      (node (ref "RWA_2") (pin "7") (pinfunction "7_7") (pintype "bidirectional"))
      (node (ref "RWA_3") (pin "7") (pinfunction "7_7") (pintype "bidirectional"))
      (node (ref "RWA_4") (pin "7") (pinfunction "7_7") (pintype "bidirectional"))
      (node (ref "SPI_TEST1") (pin "12") (pinfunction "12_12") (pintype "passive"))
      (node (ref "UART_TEST1") (pin "7") (pinfunction "7_7") (pintype "passive"))
    )
    (net (code "33") (name "I2C1_SCL") (class "Default")
      (node (ref "H1_COMM") (pin "44") (pinfunction "44_44") (pintype "passive"))
      (node (ref "H1_OBC") (pin "44") (pinfunction "44_44") (pintype "passive"))
      (node (ref "H1_PWR") (pin "44") (pinfunction "44_44") (pintype "passive"))
      (node (ref "I2C_TEST1") (pin "4") (pinfunction "4_4") (pintype "passive"))
    )
    (net (code "34") (name "I2C1_SDA") (class "Default")
      (node (ref "H1_COMM") (pin "42") (pinfunction "42_42") (pintype "passive"))
      (node (ref "H1_OBC") (pin "42") (pinfunction "42_42") (pintype "passive"))
      (node (ref "H1_PWR") (pin "42") (pinfunction "42_42") (pintype "passive"))
      (node (ref "I2C_TEST1") (pin "1") (pinfunction "1_1") (pintype "passive"))
    )
    (net (code "35") (name "I2C2_SCL") (class "Default")
      (node (ref "ARDUINO_2") (pin "3") (pinfunction "3_3") (pintype "passive"))
      (node (ref "ARDUINO_3") (pin "3") (pinfunction "3_3") (pintype "passive"))
      (node (ref "ARDUINO_4") (pin "3") (pinfunction "3_3") (pintype "passive"))
      (node (ref "H1_OBC") (pin "37") (pinfunction "37_37") (pintype "passive"))
      (node (ref "I2C_TEST1") (pin "5") (pinfunction "5_5") (pintype "passive"))
    )
    (net (code "36") (name "I2C2_SDA") (class "Default")
      (node (ref "ARDUINO_2") (pin "4") (pinfunction "4_4") (pintype "passive"))
      (node (ref "ARDUINO_3") (pin "4") (pinfunction "4_4") (pintype "passive"))
      (node (ref "ARDUINO_4") (pin "4") (pinfunction "4_4") (pintype "passive"))
      (node (ref "H1_OBC") (pin "35") (pinfunction "35_35") (pintype "passive"))
      (node (ref "I2C_TEST1") (pin "2") (pinfunction "2_2") (pintype "passive"))
    )
    (net (code "37") (name "I2C3_SCL") (class "Default")
      (node (ref "ARDUINO_5") (pin "3") (pinfunction "3_3") (pintype "passive"))
      (node (ref "CIA") (pin "6") (pinfunction "6_6") (pintype "bidirectional"))
      (node (ref "H1_OBC") (pin "51") (pinfunction "51_51") (pintype "passive"))
      (node (ref "I2C_TEST1") (pin "6") (pinfunction "6_6") (pintype "passive"))
    )
    (net (code "38") (name "I2C3_SDA") (class "Default")
      (node (ref "ARDUINO_5") (pin "4") (pinfunction "4_4") (pintype "passive"))
      (node (ref "CIA") (pin "7") (pinfunction "7_7") (pintype "bidirectional"))
      (node (ref "H1_OBC") (pin "49") (pinfunction "49_49") (pintype "passive"))
      (node (ref "I2C_TEST1") (pin "3") (pinfunction "3_3") (pintype "passive"))
    )
    (net (code "39") (name "N$11") (class "Default")
      (node (ref "CIA") (pin "9") (pinfunction "9_9") (pintype "bidirectional"))
    )
    (net (code "40") (name "N$12") (class "Default")
      (node (ref "CIA") (pin "10") (pinfunction "10_10") (pintype "bidirectional"))
    )
    (net (code "41") (name "Net-(LED1-C)") (class "Default")
      (node (ref "LED1") (pin "K") (pinfunction "C_K") (pintype "passive"))
      (node (ref "R1") (pin "1") (pinfunction "1_1") (pintype "passive"))
    )
    (net (code "42") (name "Net-(LED2-C)") (class "Default")
      (node (ref "LED2") (pin "K") (pinfunction "C_K") (pintype "passive"))
      (node (ref "R2") (pin "1") (pinfunction "1_1") (pintype "passive"))
    )
    (net (code "43") (name "Net-(LED3-C)") (class "Default")
      (node (ref "LED3") (pin "K") (pinfunction "C_K") (pintype "passive"))
      (node (ref "R3") (pin "1") (pinfunction "1_1") (pintype "passive"))
    )
    (net (code "44") (name "Net-(LED4-C)") (class "Default")
      (node (ref "LED4") (pin "K") (pinfunction "C_K") (pintype "passive"))
      (node (ref "R4") (pin "1") (pinfunction "1_1") (pintype "passive"))
    )
    (net (code "45") (name "Net-(LED5-C)") (class "Default")
      (node (ref "LED5") (pin "K") (pinfunction "C_K") (pintype "passive"))
      (node (ref "R5") (pin "1") (pinfunction "1_1") (pintype "passive"))
    )
    (net (code "46") (name "PCM_IN") (class "Default")
      (node (ref "H2_OBC") (pin "35") (pinfunction "35_35") (pintype "passive"))
      (node (ref "H2_OBC") (pin "36") (pinfunction "36_36") (pintype "passive"))
      (node (ref "MISC_TEST") (pin "4") (pinfunction "4_4") (pintype "passive"))
    )
    (net (code "47") (name "PH5_NEG") (class "Default")
      (node (ref "H1_COMM") (pin "38") (pinfunction "38_38") (pintype "passive"))
      (node (ref "H1_OBC") (pin "38") (pinfunction "38_38") (pintype "passive"))
      (node (ref "JP1") (pin "1") (pinfunction "1_1") (pintype "passive"))
    )
    (net (code "48") (name "PH5_POS") (class "Default")
      (node (ref "H1_COMM") (pin "36") (pinfunction "36_36") (pintype "passive"))
      (node (ref "H1_OBC") (pin "36") (pinfunction "36_36") (pintype "passive"))
      (node (ref "JP1") (pin "2") (pinfunction "2_2") (pintype "passive"))
    )
    (net (code "49") (name "SPI_EN_1") (class "Default")
      (node (ref "H1_OBC") (pin "7") (pinfunction "7_7") (pintype "passive"))
      (node (ref "RWA_1") (pin "2") (pinfunction "2_2") (pintype "bidirectional"))
      (node (ref "SPI_TEST1") (pin "1") (pinfunction "1_1") (pintype "passive"))
    )
    (net (code "50") (name "SPI_EN_2") (class "Default")
      (node (ref "H1_OBC") (pin "8") (pinfunction "8_8") (pintype "passive"))
      (node (ref "RWA_2") (pin "2") (pinfunction "2_2") (pintype "bidirectional"))
      (node (ref "SPI_TEST1") (pin "2") (pinfunction "2_2") (pintype "passive"))
    )
    (net (code "51") (name "SPI_EN_3") (class "Default")
      (node (ref "H1_OBC") (pin "22") (pinfunction "22_22") (pintype "passive"))
      (node (ref "RWA_3") (pin "2") (pinfunction "2_2") (pintype "bidirectional"))
      (node (ref "SPI_TEST1") (pin "3") (pinfunction "3_3") (pintype "passive"))
    )
    (net (code "52") (name "SPI_EN_4") (class "Default")
      (node (ref "H1_OBC") (pin "21") (pinfunction "21_21") (pintype "passive"))
      (node (ref "RWA_4") (pin "2") (pinfunction "2_2") (pintype "bidirectional"))
      (node (ref "SPI_TEST1") (pin "4") (pinfunction "4_4") (pintype "passive"))
    )
    (net (code "53") (name "SPI_MISO") (class "Default")
      (node (ref "H1_OBC") (pin "18") (pinfunction "18_18") (pintype "passive"))
      (node (ref "RWA_1") (pin "4") (pinfunction "4_4") (pintype "bidirectional"))
      (node (ref "RWA_2") (pin "4") (pinfunction "4_4") (pintype "bidirectional"))
      (node (ref "RWA_3") (pin "4") (pinfunction "4_4") (pintype "bidirectional"))
      (node (ref "RWA_4") (pin "4") (pinfunction "4_4") (pintype "bidirectional"))
      (node (ref "SPI_TEST1") (pin "6") (pinfunction "6_6") (pintype "passive"))
    )
    (net (code "54") (name "SPI_MOSI") (class "Default")
      (node (ref "H1_OBC") (pin "16") (pinfunction "16_16") (pintype "passive"))
      (node (ref "RWA_1") (pin "3") (pinfunction "3_3") (pintype "bidirectional"))
      (node (ref "RWA_2") (pin "3") (pinfunction "3_3") (pintype "bidirectional"))
      (node (ref "RWA_3") (pin "3") (pinfunction "3_3") (pintype "bidirectional"))
      (node (ref "RWA_4") (pin "3") (pinfunction "3_3") (pintype "bidirectional"))
      (node (ref "SPI_TEST1") (pin "5") (pinfunction "5_5") (pintype "passive"))
    )
    (net (code "55") (name "SPI_SCK") (class "Default")
      (node (ref "H1_OBC") (pin "12") (pinfunction "12_12") (pintype "passive"))
      (node (ref "RWA_1") (pin "5") (pinfunction "5_5") (pintype "bidirectional"))
      (node (ref "RWA_2") (pin "5") (pinfunction "5_5") (pintype "bidirectional"))
      (node (ref "RWA_3") (pin "5") (pinfunction "5_5") (pintype "bidirectional"))
      (node (ref "RWA_4") (pin "5") (pinfunction "5_5") (pintype "bidirectional"))
      (node (ref "SPI_TEST1") (pin "7") (pinfunction "7_7") (pintype "passive"))
    )
    (net (code "56") (name "SPI_SS_1") (class "Default")
      (node (ref "H1_OBC") (pin "9") (pinfunction "9_9") (pintype "passive"))
      (node (ref "RWA_1") (pin "6") (pinfunction "6_6") (pintype "bidirectional"))
      (node (ref "SPI_TEST1") (pin "8") (pinfunction "8_8") (pintype "passive"))
    )
    (net (code "57") (name "SPI_SS_2") (class "Default")
      (node (ref "H1_OBC") (pin "10") (pinfunction "10_10") (pintype "passive"))
      (node (ref "RWA_2") (pin "6") (pinfunction "6_6") (pintype "bidirectional"))
      (node (ref "SPI_TEST1") (pin "9") (pinfunction "9_9") (pintype "passive"))
    )
    (net (code "58") (name "SPI_SS_3") (class "Default")
      (node (ref "H1_OBC") (pin "20") (pinfunction "20_20") (pintype "passive"))
      (node (ref "RWA_3") (pin "6") (pinfunction "6_6") (pintype "bidirectional"))
      (node (ref "SPI_TEST1") (pin "10") (pinfunction "10_10") (pintype "passive"))
    )
    (net (code "59") (name "SPI_SS_4") (class "Default")
      (node (ref "H1_OBC") (pin "19") (pinfunction "19_19") (pintype "passive"))
      (node (ref "RWA_4") (pin "6") (pinfunction "6_6") (pintype "bidirectional"))
      (node (ref "SPI_TEST1") (pin "11") (pinfunction "11_11") (pintype "passive"))
    )
    (net (code "60") (name "UART1_RX") (class "Default")
      (node (ref "H1_COMM") (pin "4") (pinfunction "4_4") (pintype "passive"))
      (node (ref "H1_OBC") (pin "4") (pinfunction "4_4") (pintype "passive"))
      (node (ref "UART_TEST1") (pin "4") (pinfunction "4_4") (pintype "passive"))
    )
    (net (code "61") (name "UART1_TX") (class "Default")
      (node (ref "H1_COMM") (pin "2") (pinfunction "2_2") (pintype "passive"))
      (node (ref "H1_OBC") (pin "2") (pinfunction "2_2") (pintype "passive"))
      (node (ref "UART_TEST1") (pin "1") (pinfunction "1_1") (pintype "passive"))
    )
    (net (code "62") (name "UART3_RX") (class "Default")
      (node (ref "ARDUINO_1") (pin "4") (pinfunction "4_4") (pintype "passive"))
      (node (ref "H1_OBC") (pin "52") (pinfunction "52_52") (pintype "passive"))
      (node (ref "UART_TEST1") (pin "5") (pinfunction "5_5") (pintype "passive"))
    )
    (net (code "63") (name "UART3_TX") (class "Default")
      (node (ref "ARDUINO_1") (pin "3") (pinfunction "3_3") (pintype "passive"))
      (node (ref "H1_OBC") (pin "50") (pinfunction "50_50") (pintype "passive"))
      (node (ref "UART_TEST1") (pin "2") (pinfunction "2_2") (pintype "passive"))
    )
    (net (code "64") (name "UART4_RX") (class "Default")
      (node (ref "CIA") (pin "4") (pinfunction "4_4") (pintype "bidirectional"))
      (node (ref "H1_OBC") (pin "3") (pinfunction "3_3") (pintype "passive"))
      (node (ref "UART_TEST1") (pin "6") (pinfunction "6_6") (pintype "passive"))
    )
    (net (code "65") (name "UART4_TX") (class "Default")
      (node (ref "CIA") (pin "3") (pinfunction "3_3") (pintype "bidirectional"))
      (node (ref "H1_OBC") (pin "1") (pinfunction "1_1") (pintype "passive"))
      (node (ref "UART_TEST1") (pin "3") (pinfunction "3_3") (pintype "passive"))
    )
    (net (code "66") (name "unconnected-(ARDUINO_1_PWR-S-Pad3)") (class "Default")
      (node (ref "ARDUINO_1_PWR") (pin "3") (pinfunction "S_3") (pintype "passive"))
    )
    (net (code "67") (name "unconnected-(ARDUINO_2_PWR-S-Pad3)") (class "Default")
      (node (ref "ARDUINO_2_PWR") (pin "3") (pinfunction "S_3") (pintype "passive"))
    )
    (net (code "68") (name "unconnected-(ARDUINO_3_PWR-S-Pad3)") (class "Default")
      (node (ref "ARDUINO_3_PWR") (pin "3") (pinfunction "S_3") (pintype "passive"))
    )
    (net (code "69") (name "unconnected-(ARDUINO_4_PWR-S-Pad3)") (class "Default")
      (node (ref "ARDUINO_4_PWR") (pin "3") (pinfunction "S_3") (pintype "passive"))
    )
    (net (code "70") (name "unconnected-(ARDUINO_5_PWR-S-Pad3)") (class "Default")
      (node (ref "ARDUINO_5_PWR") (pin "3") (pinfunction "S_3") (pintype "passive"))
    )
    (net (code "71") (name "unconnected-(CIA-PadMP1)") (class "Default")
      (node (ref "CIA") (pin "MP1") (pinfunction "MP1_MP1") (pintype "bidirectional"))
    )
    (net (code "72") (name "unconnected-(CIA-PadMP2)") (class "Default")
      (node (ref "CIA") (pin "MP2") (pinfunction "MP2_MP2") (pintype "bidirectional"))
    )
    (net (code "73") (name "unconnected-(H1_COMM-Pad1)") (class "Default")
      (node (ref "H1_COMM") (pin "1") (pinfunction "1_1") (pintype "passive"))
    )
    (net (code "74") (name "unconnected-(H1_COMM-Pad3)") (class "Default")
      (node (ref "H1_COMM") (pin "3") (pinfunction "3_3") (pintype "passive"))
    )
    (net (code "75") (name "unconnected-(H1_COMM-Pad5)") (class "Default")
      (node (ref "H1_COMM") (pin "5") (pinfunction "5_5") (pintype "passive"))
    )
    (net (code "76") (name "unconnected-(H1_COMM-Pad6)") (class "Default")
      (node (ref "H1_COMM") (pin "6") (pinfunction "6_6") (pintype "passive"))
    )
    (net (code "77") (name "unconnected-(H1_COMM-Pad7)") (class "Default")
      (node (ref "H1_COMM") (pin "7") (pinfunction "7_7") (pintype "passive"))
    )
    (net (code "78") (name "unconnected-(H1_COMM-Pad8)") (class "Default")
      (node (ref "H1_COMM") (pin "8") (pinfunction "8_8") (pintype "passive"))
    )
    (net (code "79") (name "unconnected-(H1_COMM-Pad9)") (class "Default")
      (node (ref "H1_COMM") (pin "9") (pinfunction "9_9") (pintype "passive"))
    )
    (net (code "80") (name "unconnected-(H1_COMM-Pad10)") (class "Default")
      (node (ref "H1_COMM") (pin "10") (pinfunction "10_10") (pintype "passive"))
    )
    (net (code "81") (name "unconnected-(H1_COMM-Pad11)") (class "Default")
      (node (ref "H1_COMM") (pin "11") (pinfunction "11_11") (pintype "passive"))
    )
    (net (code "82") (name "unconnected-(H1_COMM-Pad12)") (class "Default")
      (node (ref "H1_COMM") (pin "12") (pinfunction "12_12") (pintype "passive"))
    )
    (net (code "83") (name "unconnected-(H1_COMM-Pad13)") (class "Default")
      (node (ref "H1_COMM") (pin "13") (pinfunction "13_13") (pintype "passive"))
    )
    (net (code "84") (name "unconnected-(H1_COMM-Pad14)") (class "Default")
      (node (ref "H1_COMM") (pin "14") (pinfunction "14_14") (pintype "passive"))
    )
    (net (code "85") (name "unconnected-(H1_COMM-Pad15)") (class "Default")
      (node (ref "H1_COMM") (pin "15") (pinfunction "15_15") (pintype "passive"))
    )
    (net (code "86") (name "unconnected-(H1_COMM-Pad16)") (class "Default")
      (node (ref "H1_COMM") (pin "16") (pinfunction "16_16") (pintype "passive"))
    )
    (net (code "87") (name "unconnected-(H1_COMM-Pad17)") (class "Default")
      (node (ref "H1_COMM") (pin "17") (pinfunction "17_17") (pintype "passive"))
    )
    (net (code "88") (name "unconnected-(H1_COMM-Pad18)") (class "Default")
      (node (ref "H1_COMM") (pin "18") (pinfunction "18_18") (pintype "passive"))
    )
    (net (code "89") (name "unconnected-(H1_COMM-Pad19)") (class "Default")
      (node (ref "H1_COMM") (pin "19") (pinfunction "19_19") (pintype "passive"))
    )
    (net (code "90") (name "unconnected-(H1_COMM-Pad20)") (class "Default")
      (node (ref "H1_COMM") (pin "20") (pinfunction "20_20") (pintype "passive"))
    )
    (net (code "91") (name "unconnected-(H1_COMM-Pad21)") (class "Default")
      (node (ref "H1_COMM") (pin "21") (pinfunction "21_21") (pintype "passive"))
    )
    (net (code "92") (name "unconnected-(H1_COMM-Pad22)") (class "Default")
      (node (ref "H1_COMM") (pin "22") (pinfunction "22_22") (pintype "passive"))
    )
    (net (code "93") (name "unconnected-(H1_COMM-Pad24)") (class "Default")
      (node (ref "H1_COMM") (pin "24") (pinfunction "24_24") (pintype "passive"))
    )
    (net (code "94") (name "unconnected-(H1_COMM-Pad26)") (class "Default")
      (node (ref "H1_COMM") (pin "26") (pinfunction "26_26") (pintype "passive"))
    )
    (net (code "95") (name "unconnected-(H1_COMM-Pad27)") (class "Default")
      (node (ref "H1_COMM") (pin "27") (pinfunction "27_27") (pintype "passive"))
    )
    (net (code "96") (name "unconnected-(H1_COMM-Pad28)") (class "Default")
      (node (ref "H1_COMM") (pin "28") (pinfunction "28_28") (pintype "passive"))
    )
    (net (code "97") (name "unconnected-(H1_COMM-Pad29)") (class "Default")
      (node (ref "H1_COMM") (pin "29") (pinfunction "29_29") (pintype "passive"))
    )
    (net (code "98") (name "unconnected-(H1_COMM-Pad30)") (class "Default")
      (node (ref "H1_COMM") (pin "30") (pinfunction "30_30") (pintype "passive"))
    )
    (net (code "99") (name "unconnected-(H1_COMM-Pad31)") (class "Default")
      (node (ref "H1_COMM") (pin "31") (pinfunction "31_31") (pintype "passive"))
    )
    (net (code "100") (name "unconnected-(H1_COMM-Pad32)") (class "Default")
      (node (ref "H1_COMM") (pin "32") (pinfunction "32_32") (pintype "passive"))
    )
    (net (code "101") (name "unconnected-(H1_COMM-Pad33)") (class "Default")
      (node (ref "H1_COMM") (pin "33") (pinfunction "33_33") (pintype "passive"))
    )
    (net (code "102") (name "unconnected-(H1_COMM-Pad34)") (class "Default")
      (node (ref "H1_COMM") (pin "34") (pinfunction "34_34") (pintype "passive"))
    )
    (net (code "103") (name "unconnected-(H1_COMM-Pad35)") (class "Default")
      (node (ref "H1_COMM") (pin "35") (pinfunction "35_35") (pintype "passive"))
    )
    (net (code "104") (name "unconnected-(H1_COMM-Pad37)") (class "Default")
      (node (ref "H1_COMM") (pin "37") (pinfunction "37_37") (pintype "passive"))
    )
    (net (code "105") (name "unconnected-(H1_COMM-Pad39)") (class "Default")
      (node (ref "H1_COMM") (pin "39") (pinfunction "39_39") (pintype "passive"))
    )
    (net (code "106") (name "unconnected-(H1_COMM-Pad40)") (class "Default")
      (node (ref "H1_COMM") (pin "40") (pinfunction "40_40") (pintype "passive"))
    )
    (net (code "107") (name "unconnected-(H1_COMM-Pad41)") (class "Default")
      (node (ref "H1_COMM") (pin "41") (pinfunction "41_41") (pintype "passive"))
    )
    (net (code "108") (name "unconnected-(H1_COMM-Pad43)") (class "Default")
      (node (ref "H1_COMM") (pin "43") (pinfunction "43_43") (pintype "passive"))
    )
    (net (code "109") (name "unconnected-(H1_COMM-Pad45)") (class "Default")
      (node (ref "H1_COMM") (pin "45") (pinfunction "45_45") (pintype "passive"))
    )
    (net (code "110") (name "unconnected-(H1_COMM-Pad46)") (class "Default")
      (node (ref "H1_COMM") (pin "46") (pinfunction "46_46") (pintype "passive"))
    )
    (net (code "111") (name "unconnected-(H1_COMM-Pad47)") (class "Default")
      (node (ref "H1_COMM") (pin "47") (pinfunction "47_47") (pintype "passive"))
    )
    (net (code "112") (name "unconnected-(H1_COMM-Pad48)") (class "Default")
      (node (ref "H1_COMM") (pin "48") (pinfunction "48_48") (pintype "passive"))
    )
    (net (code "113") (name "unconnected-(H1_COMM-Pad49)") (class "Default")
      (node (ref "H1_COMM") (pin "49") (pinfunction "49_49") (pintype "passive"))
    )
    (net (code "114") (name "unconnected-(H1_COMM-Pad50)") (class "Default")
      (node (ref "H1_COMM") (pin "50") (pinfunction "50_50") (pintype "passive"))
    )
    (net (code "115") (name "unconnected-(H1_COMM-Pad51)") (class "Default")
      (node (ref "H1_COMM") (pin "51") (pinfunction "51_51") (pintype "passive"))
    )
    (net (code "116") (name "unconnected-(H1_COMM-Pad52)") (class "Default")
      (node (ref "H1_COMM") (pin "52") (pinfunction "52_52") (pintype "passive"))
    )
    (net (code "117") (name "unconnected-(H1_OBC-Pad6)") (class "Default")
      (node (ref "H1_OBC") (pin "6") (pinfunction "6_6") (pintype "passive"))
    )
    (net (code "118") (name "unconnected-(H1_OBC-Pad11)") (class "Default")
      (node (ref "H1_OBC") (pin "11") (pinfunction "11_11") (pintype "passive"))
    )
    (net (code "119") (name "unconnected-(H1_OBC-Pad13)") (class "Default")
      (node (ref "H1_OBC") (pin "13") (pinfunction "13_13") (pintype "passive"))
    )
    (net (code "120") (name "unconnected-(H1_OBC-Pad14)") (class "Default")
      (node (ref "H1_OBC") (pin "14") (pinfunction "14_14") (pintype "passive"))
    )
    (net (code "121") (name "unconnected-(H1_OBC-Pad15)") (class "Default")
      (node (ref "H1_OBC") (pin "15") (pinfunction "15_15") (pintype "passive"))
    )
    (net (code "122") (name "unconnected-(H1_OBC-Pad17)") (class "Default")
      (node (ref "H1_OBC") (pin "17") (pinfunction "17_17") (pintype "passive"))
    )
    (net (code "123") (name "unconnected-(H1_OBC-Pad24)") (class "Default")
      (node (ref "H1_OBC") (pin "24") (pinfunction "24_24") (pintype "passive"))
    )
    (net (code "124") (name "unconnected-(H1_OBC-Pad26)") (class "Default")
      (node (ref "H1_OBC") (pin "26") (pinfunction "26_26") (pintype "passive"))
    )
    (net (code "125") (name "unconnected-(H1_OBC-Pad27)") (class "Default")
      (node (ref "H1_OBC") (pin "27") (pinfunction "27_27") (pintype "passive"))
    )
    (net (code "126") (name "unconnected-(H1_OBC-Pad28)") (class "Default")
      (node (ref "H1_OBC") (pin "28") (pinfunction "28_28") (pintype "passive"))
    )
    (net (code "127") (name "unconnected-(H1_OBC-Pad29)") (class "Default")
      (node (ref "H1_OBC") (pin "29") (pinfunction "29_29") (pintype "passive"))
    )
    (net (code "128") (name "unconnected-(H1_OBC-Pad30)") (class "Default")
      (node (ref "H1_OBC") (pin "30") (pinfunction "30_30") (pintype "passive"))
    )
    (net (code "129") (name "unconnected-(H1_OBC-Pad31)") (class "Default")
      (node (ref "H1_OBC") (pin "31") (pinfunction "31_31") (pintype "passive"))
    )
    (net (code "130") (name "unconnected-(H1_OBC-Pad32)") (class "Default")
      (node (ref "H1_OBC") (pin "32") (pinfunction "32_32") (pintype "passive"))
    )
    (net (code "131") (name "unconnected-(H1_OBC-Pad33)") (class "Default")
      (node (ref "H1_OBC") (pin "33") (pinfunction "33_33") (pintype "passive"))
    )
    (net (code "132") (name "unconnected-(H1_OBC-Pad34)") (class "Default")
      (node (ref "H1_OBC") (pin "34") (pinfunction "34_34") (pintype "passive"))
    )
    (net (code "133") (name "unconnected-(H1_OBC-Pad39)") (class "Default")
      (node (ref "H1_OBC") (pin "39") (pinfunction "39_39") (pintype "passive"))
    )
    (net (code "134") (name "unconnected-(H1_OBC-Pad40)") (class "Default")
      (node (ref "H1_OBC") (pin "40") (pinfunction "40_40") (pintype "passive"))
    )
    (net (code "135") (name "unconnected-(H1_OBC-Pad41)") (class "Default")
      (node (ref "H1_OBC") (pin "41") (pinfunction "41_41") (pintype "passive"))
    )
    (net (code "136") (name "unconnected-(H1_OBC-Pad43)") (class "Default")
      (node (ref "H1_OBC") (pin "43") (pinfunction "43_43") (pintype "passive"))
    )
    (net (code "137") (name "unconnected-(H1_OBC-Pad45)") (class "Default")
      (node (ref "H1_OBC") (pin "45") (pinfunction "45_45") (pintype "passive"))
    )
    (net (code "138") (name "unconnected-(H1_OBC-Pad46)") (class "Default")
      (node (ref "H1_OBC") (pin "46") (pinfunction "46_46") (pintype "passive"))
    )
    (net (code "139") (name "unconnected-(H1_OBC-Pad47)") (class "Default")
      (node (ref "H1_OBC") (pin "47") (pinfunction "47_47") (pintype "passive"))
    )
    (net (code "140") (name "unconnected-(H1_OBC-Pad48)") (class "Default")
      (node (ref "H1_OBC") (pin "48") (pinfunction "48_48") (pintype "passive"))
    )
    (net (code "141") (name "unconnected-(H1_PWR-Pad1)") (class "Default")
      (node (ref "H1_PWR") (pin "1") (pinfunction "1_1") (pintype "passive"))
    )
    (net (code "142") (name "unconnected-(H1_PWR-Pad2)") (class "Default")
      (node (ref "H1_PWR") (pin "2") (pinfunction "2_2") (pintype "passive"))
    )
    (net (code "143") (name "unconnected-(H1_PWR-Pad3)") (class "Default")
      (node (ref "H1_PWR") (pin "3") (pinfunction "3_3") (pintype "passive"))
    )
    (net (code "144") (name "unconnected-(H1_PWR-Pad4)") (class "Default")
      (node (ref "H1_PWR") (pin "4") (pinfunction "4_4") (pintype "passive"))
    )
    (net (code "145") (name "unconnected-(H1_PWR-Pad5)") (class "Default")
      (node (ref "H1_PWR") (pin "5") (pinfunction "5_5") (pintype "passive"))
    )
    (net (code "146") (name "unconnected-(H1_PWR-Pad6)") (class "Default")
      (node (ref "H1_PWR") (pin "6") (pinfunction "6_6") (pintype "passive"))
    )
    (net (code "147") (name "unconnected-(H1_PWR-Pad7)") (class "Default")
      (node (ref "H1_PWR") (pin "7") (pinfunction "7_7") (pintype "passive"))
    )
    (net (code "148") (name "unconnected-(H1_PWR-Pad8)") (class "Default")
      (node (ref "H1_PWR") (pin "8") (pinfunction "8_8") (pintype "passive"))
    )
    (net (code "149") (name "unconnected-(H1_PWR-Pad9)") (class "Default")
      (node (ref "H1_PWR") (pin "9") (pinfunction "9_9") (pintype "passive"))
    )
    (net (code "150") (name "unconnected-(H1_PWR-Pad10)") (class "Default")
      (node (ref "H1_PWR") (pin "10") (pinfunction "10_10") (pintype "passive"))
    )
    (net (code "151") (name "unconnected-(H1_PWR-Pad11)") (class "Default")
      (node (ref "H1_PWR") (pin "11") (pinfunction "11_11") (pintype "passive"))
    )
    (net (code "152") (name "unconnected-(H1_PWR-Pad12)") (class "Default")
      (node (ref "H1_PWR") (pin "12") (pinfunction "12_12") (pintype "passive"))
    )
    (net (code "153") (name "unconnected-(H1_PWR-Pad13)") (class "Default")
      (node (ref "H1_PWR") (pin "13") (pinfunction "13_13") (pintype "passive"))
    )
    (net (code "154") (name "unconnected-(H1_PWR-Pad14)") (class "Default")
      (node (ref "H1_PWR") (pin "14") (pinfunction "14_14") (pintype "passive"))
    )
    (net (code "155") (name "unconnected-(H1_PWR-Pad15)") (class "Default")
      (node (ref "H1_PWR") (pin "15") (pinfunction "15_15") (pintype "passive"))
    )
    (net (code "156") (name "unconnected-(H1_PWR-Pad16)") (class "Default")
      (node (ref "H1_PWR") (pin "16") (pinfunction "16_16") (pintype "passive"))
    )
    (net (code "157") (name "unconnected-(H1_PWR-Pad17)") (class "Default")
      (node (ref "H1_PWR") (pin "17") (pinfunction "17_17") (pintype "passive"))
    )
    (net (code "158") (name "unconnected-(H1_PWR-Pad18)") (class "Default")
      (node (ref "H1_PWR") (pin "18") (pinfunction "18_18") (pintype "passive"))
    )
    (net (code "159") (name "unconnected-(H1_PWR-Pad19)") (class "Default")
      (node (ref "H1_PWR") (pin "19") (pinfunction "19_19") (pintype "passive"))
    )
    (net (code "160") (name "unconnected-(H1_PWR-Pad20)") (class "Default")
      (node (ref "H1_PWR") (pin "20") (pinfunction "20_20") (pintype "passive"))
    )
    (net (code "161") (name "unconnected-(H1_PWR-Pad21)") (class "Default")
      (node (ref "H1_PWR") (pin "21") (pinfunction "21_21") (pintype "passive"))
    )
    (net (code "162") (name "unconnected-(H1_PWR-Pad22)") (class "Default")
      (node (ref "H1_PWR") (pin "22") (pinfunction "22_22") (pintype "passive"))
    )
    (net (code "163") (name "unconnected-(H1_PWR-Pad23)") (class "Default")
      (node (ref "H1_PWR") (pin "23") (pinfunction "23_23") (pintype "passive"))
    )
    (net (code "164") (name "unconnected-(H1_PWR-Pad24)") (class "Default")
      (node (ref "H1_PWR") (pin "24") (pinfunction "24_24") (pintype "passive"))
    )
    (net (code "165") (name "unconnected-(H1_PWR-Pad25)") (class "Default")
      (node (ref "H1_PWR") (pin "25") (pinfunction "25_25") (pintype "passive"))
    )
    (net (code "166") (name "unconnected-(H1_PWR-Pad26)") (class "Default")
      (node (ref "H1_PWR") (pin "26") (pinfunction "26_26") (pintype "passive"))
    )
    (net (code "167") (name "unconnected-(H1_PWR-Pad27)") (class "Default")
      (node (ref "H1_PWR") (pin "27") (pinfunction "27_27") (pintype "passive"))
    )
    (net (code "168") (name "unconnected-(H1_PWR-Pad28)") (class "Default")
      (node (ref "H1_PWR") (pin "28") (pinfunction "28_28") (pintype "passive"))
    )
    (net (code "169") (name "unconnected-(H1_PWR-Pad29)") (class "Default")
      (node (ref "H1_PWR") (pin "29") (pinfunction "29_29") (pintype "passive"))
    )
    (net (code "170") (name "unconnected-(H1_PWR-Pad30)") (class "Default")
      (node (ref "H1_PWR") (pin "30") (pinfunction "30_30") (pintype "passive"))
    )
    (net (code "171") (name "unconnected-(H1_PWR-Pad31)") (class "Default")
      (node (ref "H1_PWR") (pin "31") (pinfunction "31_31") (pintype "passive"))
    )
    (net (code "172") (name "unconnected-(H1_PWR-Pad32)") (class "Default")
      (node (ref "H1_PWR") (pin "32") (pinfunction "32_32") (pintype "passive"))
    )
    (net (code "173") (name "unconnected-(H1_PWR-Pad33)") (class "Default")
      (node (ref "H1_PWR") (pin "33") (pinfunction "33_33") (pintype "passive"))
    )
    (net (code "174") (name "unconnected-(H1_PWR-Pad34)") (class "Default")
      (node (ref "H1_PWR") (pin "34") (pinfunction "34_34") (pintype "passive"))
    )
    (net (code "175") (name "unconnected-(H1_PWR-Pad35)") (class "Default")
      (node (ref "H1_PWR") (pin "35") (pinfunction "35_35") (pintype "passive"))
    )
    (net (code "176") (name "unconnected-(H1_PWR-Pad36)") (class "Default")
      (node (ref "H1_PWR") (pin "36") (pinfunction "36_36") (pintype "passive"))
    )
    (net (code "177") (name "unconnected-(H1_PWR-Pad37)") (class "Default")
      (node (ref "H1_PWR") (pin "37") (pinfunction "37_37") (pintype "passive"))
    )
    (net (code "178") (name "unconnected-(H1_PWR-Pad38)") (class "Default")
      (node (ref "H1_PWR") (pin "38") (pinfunction "38_38") (pintype "passive"))
    )
    (net (code "179") (name "unconnected-(H1_PWR-Pad39)") (class "Default")
      (node (ref "H1_PWR") (pin "39") (pinfunction "39_39") (pintype "passive"))
    )
    (net (code "180") (name "unconnected-(H1_PWR-Pad40)") (class "Default")
      (node (ref "H1_PWR") (pin "40") (pinfunction "40_40") (pintype "passive"))
    )
    (net (code "181") (name "unconnected-(H1_PWR-Pad41)") (class "Default")
      (node (ref "H1_PWR") (pin "41") (pinfunction "41_41") (pintype "passive"))
    )
    (net (code "182") (name "unconnected-(H1_PWR-Pad43)") (class "Default")
      (node (ref "H1_PWR") (pin "43") (pinfunction "43_43") (pintype "passive"))
    )
    (net (code "183") (name "unconnected-(H1_PWR-Pad45)") (class "Default")
      (node (ref "H1_PWR") (pin "45") (pinfunction "45_45") (pintype "passive"))
    )
    (net (code "184") (name "unconnected-(H1_PWR-Pad46)") (class "Default")
      (node (ref "H1_PWR") (pin "46") (pinfunction "46_46") (pintype "passive"))
    )
    (net (code "185") (name "unconnected-(H1_PWR-Pad47)") (class "Default")
      (node (ref "H1_PWR") (pin "47") (pinfunction "47_47") (pintype "passive"))
    )
    (net (code "186") (name "unconnected-(H1_PWR-Pad48)") (class "Default")
      (node (ref "H1_PWR") (pin "48") (pinfunction "48_48") (pintype "passive"))
    )
    (net (code "187") (name "unconnected-(H1_PWR-Pad49)") (class "Default")
      (node (ref "H1_PWR") (pin "49") (pinfunction "49_49") (pintype "passive"))
    )
    (net (code "188") (name "unconnected-(H1_PWR-Pad50)") (class "Default")
      (node (ref "H1_PWR") (pin "50") (pinfunction "50_50") (pintype "passive"))
    )
    (net (code "189") (name "unconnected-(H1_PWR-Pad51)") (class "Default")
      (node (ref "H1_PWR") (pin "51") (pinfunction "51_51") (pintype "passive"))
    )
    (net (code "190") (name "unconnected-(H1_PWR-Pad52)") (class "Default")
      (node (ref "H1_PWR") (pin "52") (pinfunction "52_52") (pintype "passive"))
    )
    (net (code "191") (name "unconnected-(H2_COMM-Pad1)") (class "Default")
      (node (ref "H2_COMM") (pin "1") (pinfunction "1_1") (pintype "passive"))
    )
    (net (code "192") (name "unconnected-(H2_COMM-Pad2)") (class "Default")
      (node (ref "H2_COMM") (pin "2") (pinfunction "2_2") (pintype "passive"))
    )
    (net (code "193") (name "unconnected-(H2_COMM-Pad3)") (class "Default")
      (node (ref "H2_COMM") (pin "3") (pinfunction "3_3") (pintype "passive"))
    )
    (net (code "194") (name "unconnected-(H2_COMM-Pad4)") (class "Default")
      (node (ref "H2_COMM") (pin "4") (pinfunction "4_4") (pintype "passive"))
    )
    (net (code "195") (name "unconnected-(H2_COMM-Pad5)") (class "Default")
      (node (ref "H2_COMM") (pin "5") (pinfunction "5_5") (pintype "passive"))
    )
    (net (code "196") (name "unconnected-(H2_COMM-Pad6)") (class "Default")
      (node (ref "H2_COMM") (pin "6") (pinfunction "6_6") (pintype "passive"))
    )
    (net (code "197") (name "unconnected-(H2_COMM-Pad7)") (class "Default")
      (node (ref "H2_COMM") (pin "7") (pinfunction "7_7") (pintype "passive"))
    )
    (net (code "198") (name "unconnected-(H2_COMM-Pad8)") (class "Default")
      (node (ref "H2_COMM") (pin "8") (pinfunction "8_8") (pintype "passive"))
    )
    (net (code "199") (name "unconnected-(H2_COMM-Pad9)") (class "Default")
      (node (ref "H2_COMM") (pin "9") (pinfunction "9_9") (pintype "passive"))
    )
    (net (code "200") (name "unconnected-(H2_COMM-Pad11)") (class "Default")
      (node (ref "H2_COMM") (pin "11") (pinfunction "11_11") (pintype "passive"))
    )
    (net (code "201") (name "unconnected-(H2_COMM-Pad12)") (class "Default")
      (node (ref "H2_COMM") (pin "12") (pinfunction "12_12") (pintype "passive"))
    )
    (net (code "202") (name "unconnected-(H2_COMM-Pad14)") (class "Default")
      (node (ref "H2_COMM") (pin "14") (pinfunction "14_14") (pintype "passive"))
    )
    (net (code "203") (name "unconnected-(H2_COMM-Pad15)") (class "Default")
      (node (ref "H2_COMM") (pin "15") (pinfunction "15_15") (pintype "passive"))
    )
    (net (code "204") (name "unconnected-(H2_COMM-Pad16)") (class "Default")
      (node (ref "H2_COMM") (pin "16") (pinfunction "16_16") (pintype "passive"))
    )
    (net (code "205") (name "unconnected-(H2_COMM-Pad19)") (class "Default")
      (node (ref "H2_COMM") (pin "19") (pinfunction "19_19") (pintype "passive"))
    )
    (net (code "206") (name "unconnected-(H2_COMM-Pad20)") (class "Default")
      (node (ref "H2_COMM") (pin "20") (pinfunction "20_20") (pintype "passive"))
    )
    (net (code "207") (name "unconnected-(H2_COMM-Pad23)") (class "Default")
      (node (ref "H2_COMM") (pin "23") (pinfunction "23_23") (pintype "passive"))
    )
    (net (code "208") (name "unconnected-(H2_COMM-Pad24)") (class "Default")
      (node (ref "H2_COMM") (pin "24") (pinfunction "24_24") (pintype "passive"))
    )
    (net (code "209") (name "unconnected-(H2_COMM-Pad25)") (class "Default")
      (node (ref "H2_COMM") (pin "25") (pinfunction "25_25") (pintype "passive"))
    )
    (net (code "210") (name "unconnected-(H2_COMM-Pad27)") (class "Default")
      (node (ref "H2_COMM") (pin "27") (pinfunction "27_27") (pintype "passive"))
    )
    (net (code "211") (name "unconnected-(H2_COMM-Pad28)") (class "Default")
      (node (ref "H2_COMM") (pin "28") (pinfunction "28_28") (pintype "passive"))
    )
    (net (code "212") (name "unconnected-(H2_COMM-Pad32)") (class "Default")
      (node (ref "H2_COMM") (pin "32") (pinfunction "32_32") (pintype "passive"))
    )
    (net (code "213") (name "unconnected-(H2_COMM-Pad33)") (class "Default")
      (node (ref "H2_COMM") (pin "33") (pinfunction "33_33") (pintype "passive"))
    )
    (net (code "214") (name "unconnected-(H2_COMM-Pad34)") (class "Default")
      (node (ref "H2_COMM") (pin "34") (pinfunction "34_34") (pintype "passive"))
    )
    (net (code "215") (name "unconnected-(H2_COMM-Pad35)") (class "Default")
      (node (ref "H2_COMM") (pin "35") (pinfunction "35_35") (pintype "passive"))
    )
    (net (code "216") (name "unconnected-(H2_COMM-Pad36)") (class "Default")
      (node (ref "H2_COMM") (pin "36") (pinfunction "36_36") (pintype "passive"))
    )
    (net (code "217") (name "unconnected-(H2_COMM-Pad37)") (class "Default")
      (node (ref "H2_COMM") (pin "37") (pinfunction "37_37") (pintype "passive"))
    )
    (net (code "218") (name "unconnected-(H2_COMM-Pad38)") (class "Default")
      (node (ref "H2_COMM") (pin "38") (pinfunction "38_38") (pintype "passive"))
    )
    (net (code "219") (name "unconnected-(H2_COMM-Pad39)") (class "Default")
      (node (ref "H2_COMM") (pin "39") (pinfunction "39_39") (pintype "passive"))
    )
    (net (code "220") (name "unconnected-(H2_COMM-Pad40)") (class "Default")
      (node (ref "H2_COMM") (pin "40") (pinfunction "40_40") (pintype "passive"))
    )
    (net (code "221") (name "unconnected-(H2_COMM-Pad41)") (class "Default")
      (node (ref "H2_COMM") (pin "41") (pinfunction "41_41") (pintype "passive"))
    )
    (net (code "222") (name "unconnected-(H2_COMM-Pad42)") (class "Default")
      (node (ref "H2_COMM") (pin "42") (pinfunction "42_42") (pintype "passive"))
    )
    (net (code "223") (name "unconnected-(H2_COMM-Pad43)") (class "Default")
      (node (ref "H2_COMM") (pin "43") (pinfunction "43_43") (pintype "passive"))
    )
    (net (code "224") (name "unconnected-(H2_COMM-Pad44)") (class "Default")
      (node (ref "H2_COMM") (pin "44") (pinfunction "44_44") (pintype "passive"))
    )
    (net (code "225") (name "unconnected-(H2_COMM-Pad45)") (class "Default")
      (node (ref "H2_COMM") (pin "45") (pinfunction "45_45") (pintype "passive"))
    )
    (net (code "226") (name "unconnected-(H2_COMM-Pad46)") (class "Default")
      (node (ref "H2_COMM") (pin "46") (pinfunction "46_46") (pintype "passive"))
    )
    (net (code "227") (name "unconnected-(H2_COMM-Pad47)") (class "Default")
      (node (ref "H2_COMM") (pin "47") (pinfunction "47_47") (pintype "passive"))
    )
    (net (code "228") (name "unconnected-(H2_COMM-Pad48)") (class "Default")
      (node (ref "H2_COMM") (pin "48") (pinfunction "48_48") (pintype "passive"))
    )
    (net (code "229") (name "unconnected-(H2_COMM-Pad49)") (class "Default")
      (node (ref "H2_COMM") (pin "49") (pinfunction "49_49") (pintype "passive"))
    )
    (net (code "230") (name "unconnected-(H2_COMM-Pad50)") (class "Default")
      (node (ref "H2_COMM") (pin "50") (pinfunction "50_50") (pintype "passive"))
    )
    (net (code "231") (name "unconnected-(H2_COMM-Pad51)") (class "Default")
      (node (ref "H2_COMM") (pin "51") (pinfunction "51_51") (pintype "passive"))
    )
    (net (code "232") (name "unconnected-(H2_COMM-Pad52)") (class "Default")
      (node (ref "H2_COMM") (pin "52") (pinfunction "52_52") (pintype "passive"))
    )
    (net (code "233") (name "unconnected-(H2_OBC-Pad1)") (class "Default")
      (node (ref "H2_OBC") (pin "1") (pinfunction "1_1") (pintype "passive"))
    )
    (net (code "234") (name "unconnected-(H2_OBC-Pad2)") (class "Default")
      (node (ref "H2_OBC") (pin "2") (pinfunction "2_2") (pintype "passive"))
    )
    (net (code "235") (name "unconnected-(H2_OBC-Pad3)") (class "Default")
      (node (ref "H2_OBC") (pin "3") (pinfunction "3_3") (pintype "passive"))
    )
    (net (code "236") (name "unconnected-(H2_OBC-Pad4)") (class "Default")
      (node (ref "H2_OBC") (pin "4") (pinfunction "4_4") (pintype "passive"))
    )
    (net (code "237") (name "unconnected-(H2_OBC-Pad5)") (class "Default")
      (node (ref "H2_OBC") (pin "5") (pinfunction "5_5") (pintype "passive"))
    )
    (net (code "238") (name "unconnected-(H2_OBC-Pad6)") (class "Default")
      (node (ref "H2_OBC") (pin "6") (pinfunction "6_6") (pintype "passive"))
    )
    (net (code "239") (name "unconnected-(H2_OBC-Pad7)") (class "Default")
      (node (ref "H2_OBC") (pin "7") (pinfunction "7_7") (pintype "passive"))
    )
    (net (code "240") (name "unconnected-(H2_OBC-Pad8)") (class "Default")
      (node (ref "H2_OBC") (pin "8") (pinfunction "8_8") (pintype "passive"))
    )
    (net (code "241") (name "unconnected-(H2_OBC-Pad9)") (class "Default")
      (node (ref "H2_OBC") (pin "9") (pinfunction "9_9") (pintype "passive"))
    )
    (net (code "242") (name "unconnected-(H2_OBC-Pad11)") (class "Default")
      (node (ref "H2_OBC") (pin "11") (pinfunction "11_11") (pintype "passive"))
    )
    (net (code "243") (name "unconnected-(H2_OBC-Pad12)") (class "Default")
      (node (ref "H2_OBC") (pin "12") (pinfunction "12_12") (pintype "passive"))
    )
    (net (code "244") (name "unconnected-(H2_OBC-Pad32)") (class "Default")
      (node (ref "H2_OBC") (pin "32") (pinfunction "32_32") (pintype "passive"))
    )
    (net (code "245") (name "unconnected-(H2_OBC-Pad33)") (class "Default")
      (node (ref "H2_OBC") (pin "33") (pinfunction "33_33") (pintype "passive"))
    )
    (net (code "246") (name "unconnected-(H2_OBC-Pad34)") (class "Default")
      (node (ref "H2_OBC") (pin "34") (pinfunction "34_34") (pintype "passive"))
    )
    (net (code "247") (name "unconnected-(H2_OBC-Pad37)") (class "Default")
      (node (ref "H2_OBC") (pin "37") (pinfunction "37_37") (pintype "passive"))
    )
    (net (code "248") (name "unconnected-(H2_OBC-Pad38)") (class "Default")
      (node (ref "H2_OBC") (pin "38") (pinfunction "38_38") (pintype "passive"))
    )
    (net (code "249") (name "unconnected-(H2_OBC-Pad39)") (class "Default")
      (node (ref "H2_OBC") (pin "39") (pinfunction "39_39") (pintype "passive"))
    )
    (net (code "250") (name "unconnected-(H2_OBC-Pad40)") (class "Default")
      (node (ref "H2_OBC") (pin "40") (pinfunction "40_40") (pintype "passive"))
    )
    (net (code "251") (name "unconnected-(H2_OBC-Pad45)") (class "Default")
      (node (ref "H2_OBC") (pin "45") (pinfunction "45_45") (pintype "passive"))
    )
    (net (code "252") (name "unconnected-(H2_OBC-Pad46)") (class "Default")
      (node (ref "H2_OBC") (pin "46") (pinfunction "46_46") (pintype "passive"))
    )
    (net (code "253") (name "unconnected-(H2_OBC-Pad50)") (class "Default")
      (node (ref "H2_OBC") (pin "50") (pinfunction "50_50") (pintype "passive"))
    )
    (net (code "254") (name "unconnected-(H2_PWR-Pad1)") (class "Default")
      (node (ref "H2_PWR") (pin "1") (pinfunction "1_1") (pintype "passive"))
    )
    (net (code "255") (name "unconnected-(H2_PWR-Pad2)") (class "Default")
      (node (ref "H2_PWR") (pin "2") (pinfunction "2_2") (pintype "passive"))
    )
    (net (code "256") (name "unconnected-(H2_PWR-Pad3)") (class "Default")
      (node (ref "H2_PWR") (pin "3") (pinfunction "3_3") (pintype "passive"))
    )
    (net (code "257") (name "unconnected-(H2_PWR-Pad4)") (class "Default")
      (node (ref "H2_PWR") (pin "4") (pinfunction "4_4") (pintype "passive"))
    )
    (net (code "258") (name "unconnected-(H2_PWR-Pad5)") (class "Default")
      (node (ref "H2_PWR") (pin "5") (pinfunction "5_5") (pintype "passive"))
    )
    (net (code "259") (name "unconnected-(H2_PWR-Pad6)") (class "Default")
      (node (ref "H2_PWR") (pin "6") (pinfunction "6_6") (pintype "passive"))
    )
    (net (code "260") (name "unconnected-(H2_PWR-Pad7)") (class "Default")
      (node (ref "H2_PWR") (pin "7") (pinfunction "7_7") (pintype "passive"))
    )
    (net (code "261") (name "unconnected-(H2_PWR-Pad8)") (class "Default")
      (node (ref "H2_PWR") (pin "8") (pinfunction "8_8") (pintype "passive"))
    )
    (net (code "262") (name "unconnected-(H2_PWR-Pad9)") (class "Default")
      (node (ref "H2_PWR") (pin "9") (pinfunction "9_9") (pintype "passive"))
    )
    (net (code "263") (name "unconnected-(H2_PWR-Pad11)") (class "Default")
      (node (ref "H2_PWR") (pin "11") (pinfunction "11_11") (pintype "passive"))
    )
    (net (code "264") (name "unconnected-(H2_PWR-Pad12)") (class "Default")
      (node (ref "H2_PWR") (pin "12") (pinfunction "12_12") (pintype "passive"))
    )
    (net (code "265") (name "unconnected-(H2_PWR-Pad23)") (class "Default")
      (node (ref "H2_PWR") (pin "23") (pinfunction "23_23") (pintype "passive"))
    )
    (net (code "266") (name "unconnected-(H2_PWR-Pad24)") (class "Default")
      (node (ref "H2_PWR") (pin "24") (pinfunction "24_24") (pintype "passive"))
    )
    (net (code "267") (name "unconnected-(H2_PWR-Pad32)") (class "Default")
      (node (ref "H2_PWR") (pin "32") (pinfunction "32_32") (pintype "passive"))
    )
    (net (code "268") (name "unconnected-(H2_PWR-Pad33)") (class "Default")
      (node (ref "H2_PWR") (pin "33") (pinfunction "33_33") (pintype "passive"))
    )
    (net (code "269") (name "unconnected-(H2_PWR-Pad34)") (class "Default")
      (node (ref "H2_PWR") (pin "34") (pinfunction "34_34") (pintype "passive"))
    )
    (net (code "270") (name "unconnected-(H2_PWR-Pad35)") (class "Default")
      (node (ref "H2_PWR") (pin "35") (pinfunction "35_35") (pintype "passive"))
    )
    (net (code "271") (name "unconnected-(H2_PWR-Pad36)") (class "Default")
      (node (ref "H2_PWR") (pin "36") (pinfunction "36_36") (pintype "passive"))
    )
    (net (code "272") (name "unconnected-(H2_PWR-Pad37)") (class "Default")
      (node (ref "H2_PWR") (pin "37") (pinfunction "37_37") (pintype "passive"))
    )
    (net (code "273") (name "unconnected-(H2_PWR-Pad38)") (class "Default")
      (node (ref "H2_PWR") (pin "38") (pinfunction "38_38") (pintype "passive"))
    )
    (net (code "274") (name "unconnected-(H2_PWR-Pad39)") (class "Default")
      (node (ref "H2_PWR") (pin "39") (pinfunction "39_39") (pintype "passive"))
    )
    (net (code "275") (name "unconnected-(H2_PWR-Pad40)") (class "Default")
      (node (ref "H2_PWR") (pin "40") (pinfunction "40_40") (pintype "passive"))
    )
    (net (code "276") (name "unconnected-(H2_PWR-Pad41)") (class "Default")
      (node (ref "H2_PWR") (pin "41") (pinfunction "41_41") (pintype "passive"))
    )
    (net (code "277") (name "unconnected-(H2_PWR-Pad42)") (class "Default")
      (node (ref "H2_PWR") (pin "42") (pinfunction "42_42") (pintype "passive"))
    )
    (net (code "278") (name "unconnected-(H2_PWR-Pad43)") (class "Default")
      (node (ref "H2_PWR") (pin "43") (pinfunction "43_43") (pintype "passive"))
    )
    (net (code "279") (name "unconnected-(H2_PWR-Pad44)") (class "Default")
      (node (ref "H2_PWR") (pin "44") (pinfunction "44_44") (pintype "passive"))
    )
    (net (code "280") (name "unconnected-(H2_PWR-Pad45)") (class "Default")
      (node (ref "H2_PWR") (pin "45") (pinfunction "45_45") (pintype "passive"))
    )
    (net (code "281") (name "unconnected-(H2_PWR-Pad46)") (class "Default")
      (node (ref "H2_PWR") (pin "46") (pinfunction "46_46") (pintype "passive"))
    )
    (net (code "282") (name "unconnected-(H2_PWR-Pad49)") (class "Default")
      (node (ref "H2_PWR") (pin "49") (pinfunction "49_49") (pintype "passive"))
    )
    (net (code "283") (name "unconnected-(H2_PWR-Pad50)") (class "Default")
      (node (ref "H2_PWR") (pin "50") (pinfunction "50_50") (pintype "passive"))
    )
    (net (code "284") (name "unconnected-(H2_PWR-Pad52)") (class "Default")
      (node (ref "H2_PWR") (pin "52") (pinfunction "52_52") (pintype "passive"))
    )
  )
)
